# ES_Daisy_Field_Rev4.net
KiCad netlist of a schematic drawn in EAGLE
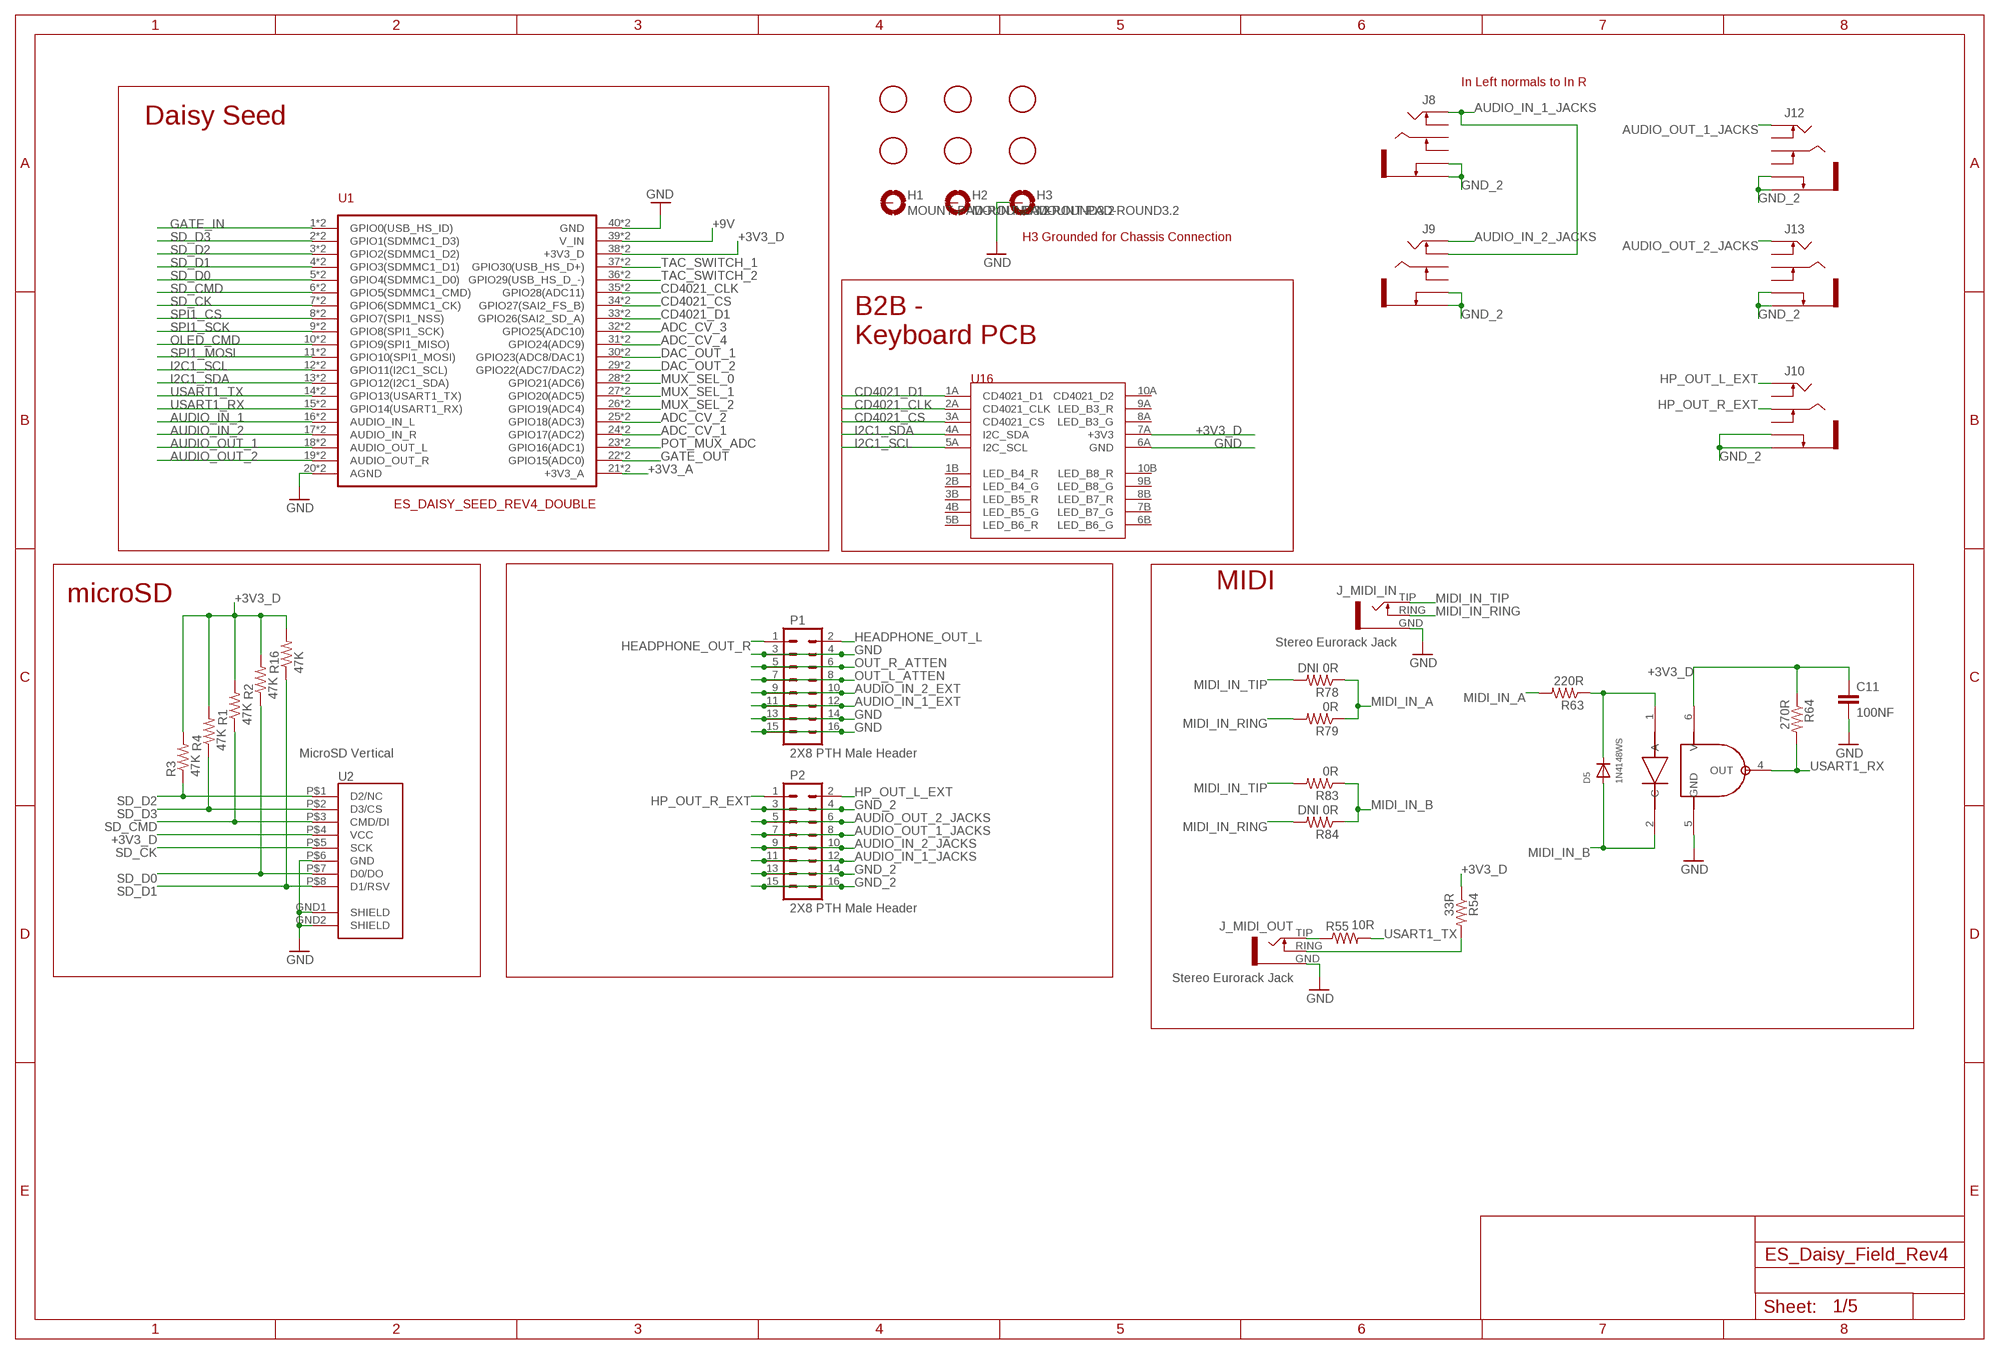
[diagram p0: schematic, sheet 1]
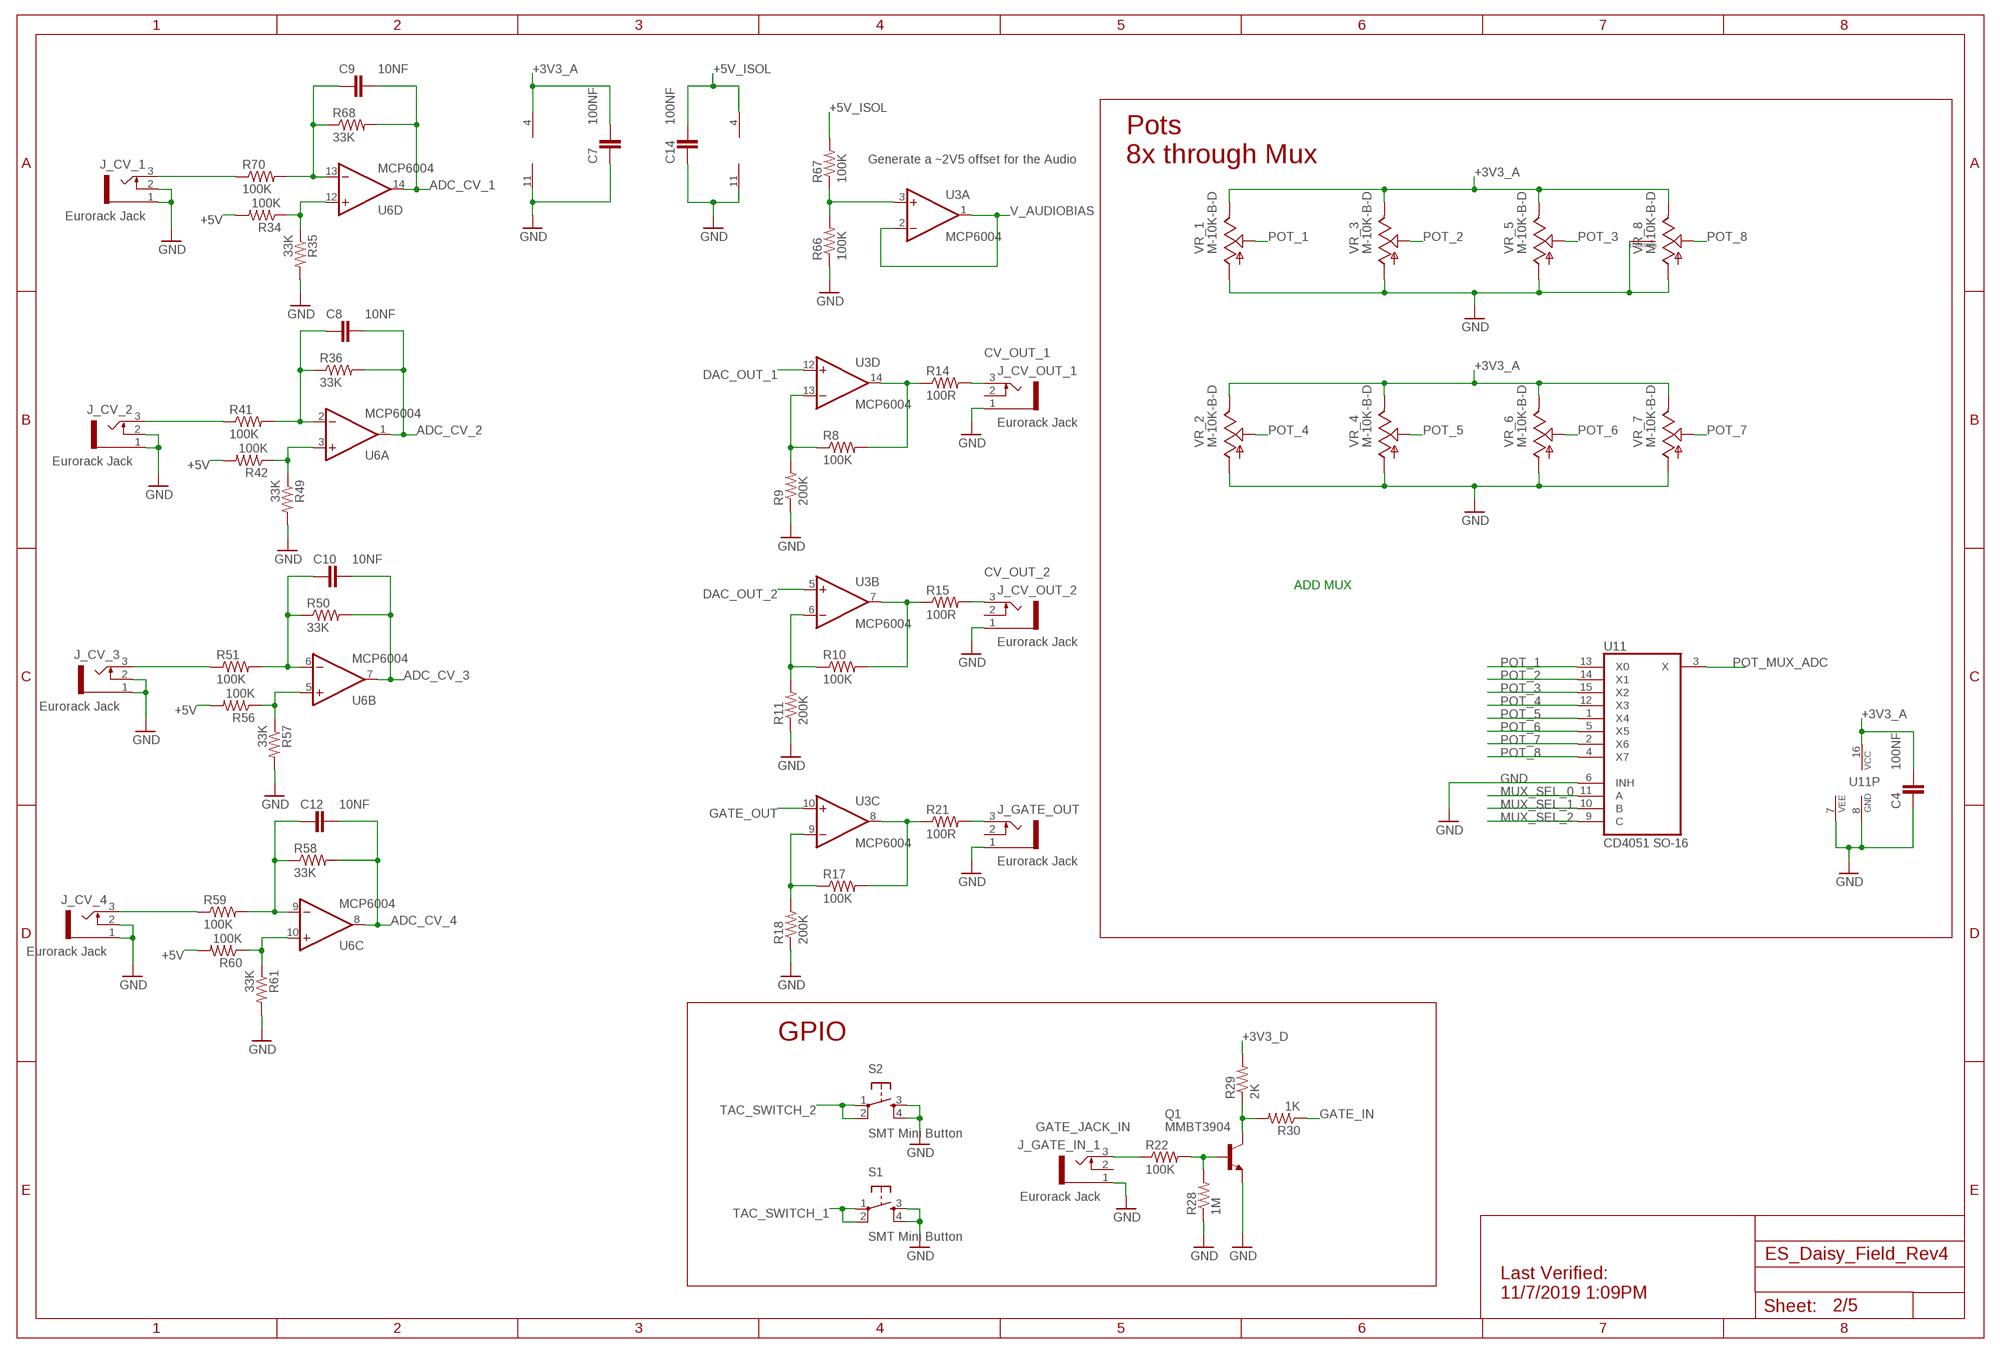
[diagram p1: schematic, sheet 2]
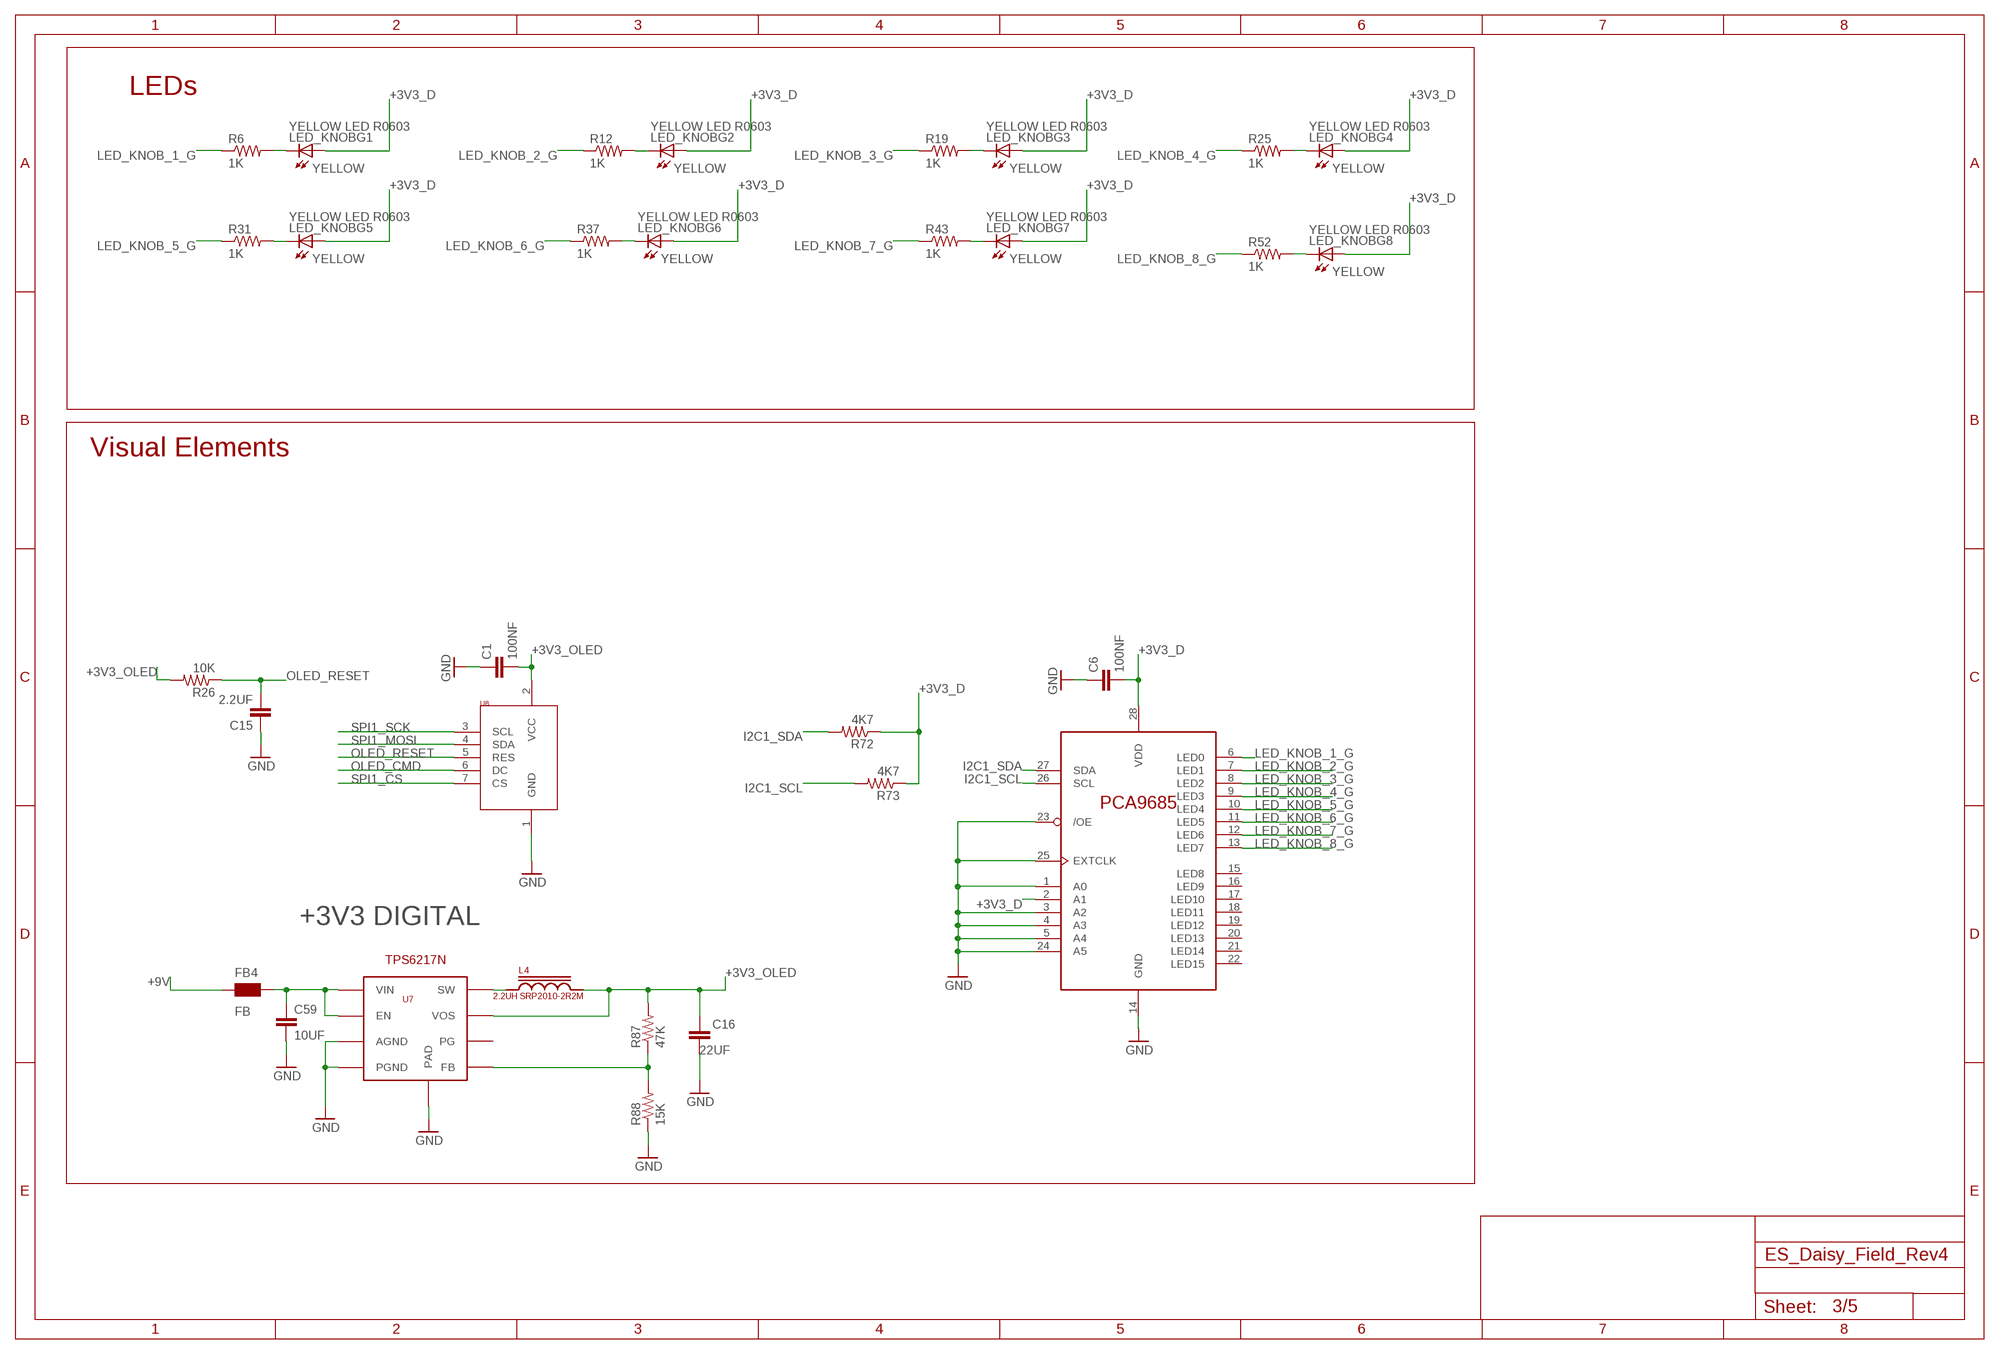
[diagram p2: schematic, sheet 3]
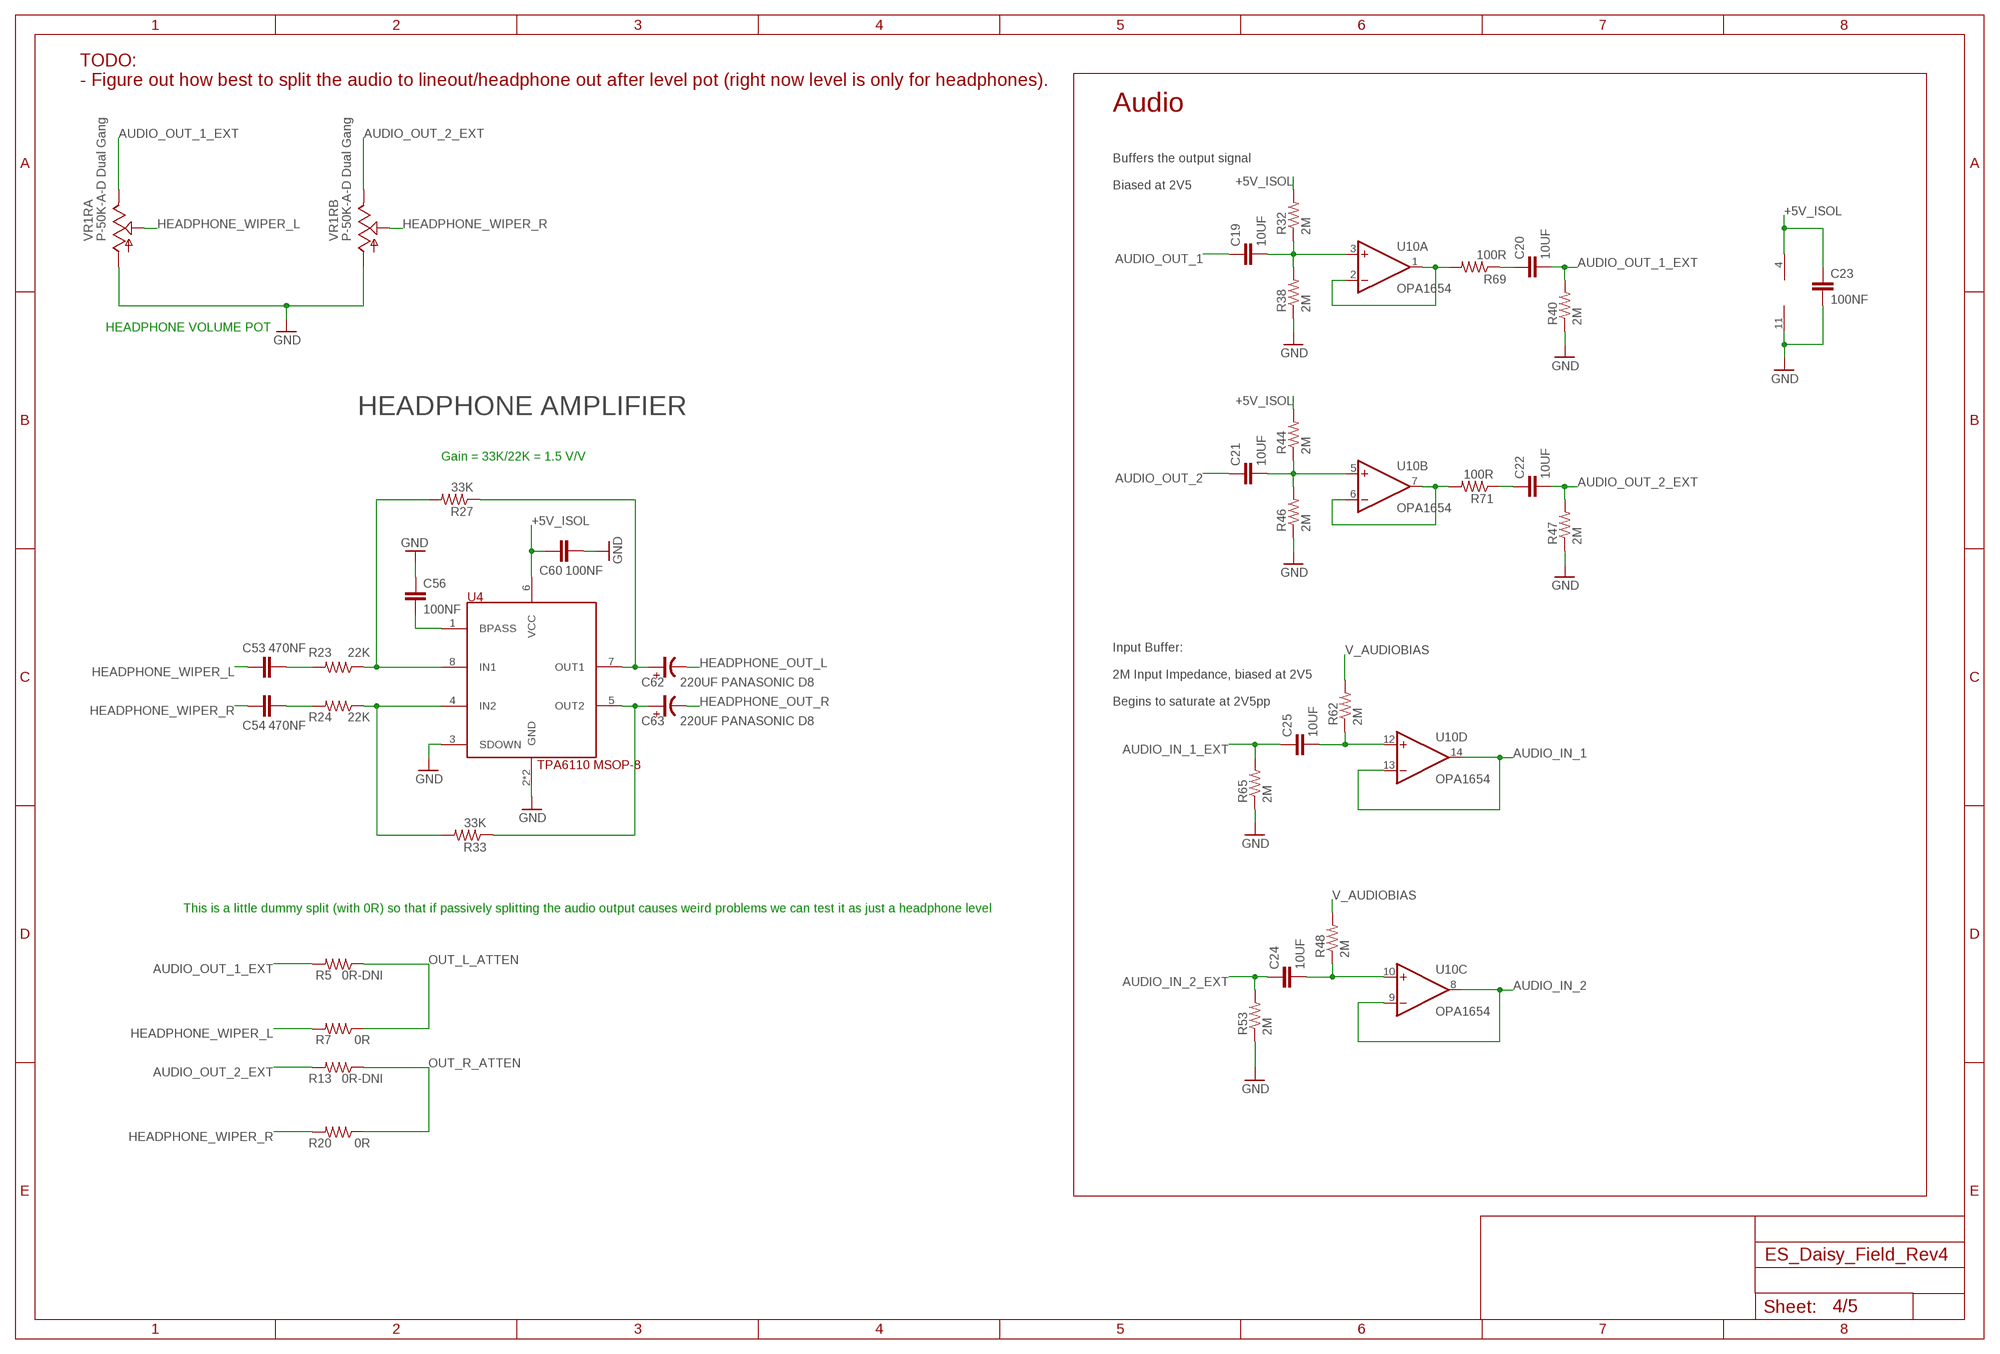
[diagram p3: schematic, sheet 4]
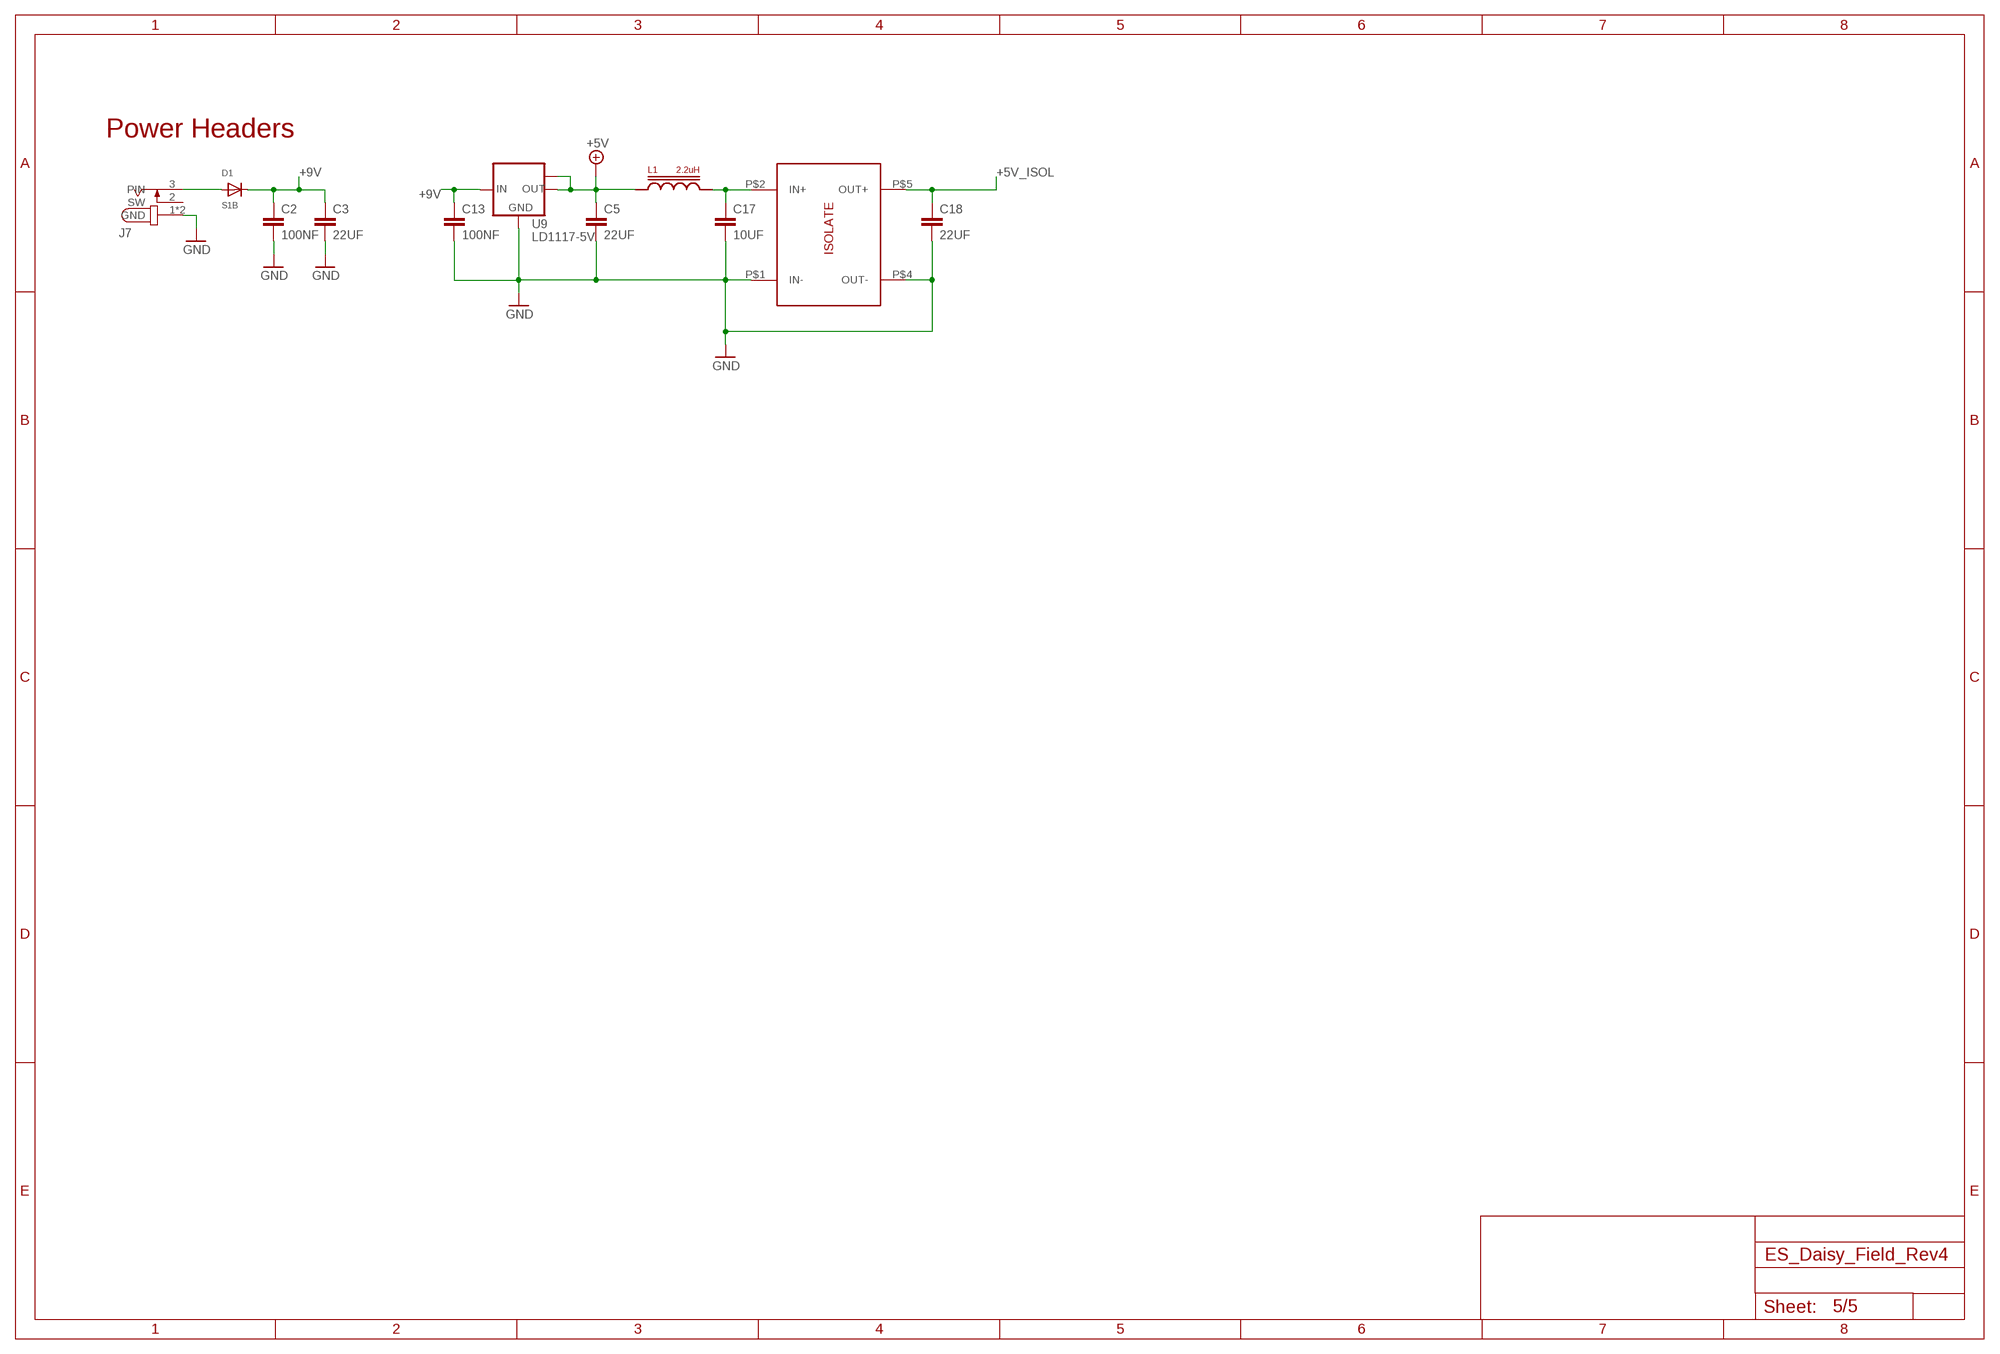
[diagram p4: schematic, sheet 5]

(export (version "E")
  (design (tool "Eeschema 10.0.6"))
  (components
    (comp (ref "C4")
      (value "100NF")
      (footprint "eagle-import:C0603")
      (libsource (lib "eagle-import") (part "C-EUC0603"))
    )
    (comp (ref "C7")
      (value "100NF")
      (footprint "eagle-import:C0603")
      (libsource (lib "eagle-import") (part "C-EUC0603"))
    )
    (comp (ref "C8")
      (value "10NF")
      (footprint "eagle-import:C0603")
      (libsource (lib "eagle-import") (part "C-EUC0603"))
    )
    (comp (ref "C9")
      (value "10NF")
      (footprint "eagle-import:C0603")
      (libsource (lib "eagle-import") (part "C-EUC0603"))
    )
    (comp (ref "C10")
      (value "10NF")
      (footprint "eagle-import:C0603")
      (libsource (lib "eagle-import") (part "C-EUC0603"))
    )
    (comp (ref "C12")
      (value "10NF")
      (footprint "eagle-import:C0603")
      (libsource (lib "eagle-import") (part "C-EUC0603"))
    )
    (comp (ref "C14")
      (value "100NF")
      (footprint "eagle-import:C0603")
      (libsource (lib "eagle-import") (part "C-EUC0603"))
    )
    (comp (ref "J_CV_1")
      (value "Eurorack Jack")
      (footprint "eagle-import:SMT_JACK")
      (libsource (lib "eagle-import") (part "EURO_JACK_SMT"))
    )
    (comp (ref "J_CV_2")
      (value "Eurorack Jack")
      (footprint "eagle-import:SMT_JACK")
      (libsource (lib "eagle-import") (part "EURO_JACK_SMT"))
    )
    (comp (ref "J_CV_3")
      (value "Eurorack Jack")
      (footprint "eagle-import:SMT_JACK")
      (libsource (lib "eagle-import") (part "EURO_JACK_SMT"))
    )
    (comp (ref "J_CV_4")
      (value "Eurorack Jack")
      (footprint "eagle-import:SMT_JACK")
      (libsource (lib "eagle-import") (part "EURO_JACK_SMT"))
    )
    (comp (ref "J_CV_OUT_1")
      (value "Eurorack Jack")
      (footprint "eagle-import:SMT_JACK")
      (libsource (lib "eagle-import") (part "EURO_JACK_SMT"))
    )
    (comp (ref "J_CV_OUT_2")
      (value "Eurorack Jack")
      (footprint "eagle-import:SMT_JACK")
      (libsource (lib "eagle-import") (part "EURO_JACK_SMT"))
    )
    (comp (ref "J_GATE_IN_1")
      (value "Eurorack Jack")
      (footprint "eagle-import:SMT_JACK")
      (libsource (lib "eagle-import") (part "EURO_JACK_SMT"))
    )
    (comp (ref "J_GATE_OUT")
      (value "Eurorack Jack")
      (footprint "eagle-import:SMT_JACK")
      (libsource (lib "eagle-import") (part "EURO_JACK_SMT"))
    )
    (comp (ref "Q1")
      (value "MMBT3904")
      (footprint "eagle-import:SOT23-BEC")
      (libsource (lib "eagle-import") (part "NPNSOT23-BEC"))
    )
    (comp (ref "R8")
      (value "100K")
      (footprint "eagle-import:R0603")
      (libsource (lib "eagle-import") (part "R-US_R0603"))
    )
    (comp (ref "R9")
      (value "200K")
      (footprint "eagle-import:R0603")
      (libsource (lib "eagle-import") (part "R-US_R0603"))
    )
    (comp (ref "R10")
      (value "100K")
      (footprint "eagle-import:R0603")
      (libsource (lib "eagle-import") (part "R-US_R0603"))
    )
    (comp (ref "R11")
      (value "200K")
      (footprint "eagle-import:R0603")
      (libsource (lib "eagle-import") (part "R-US_R0603"))
    )
    (comp (ref "R14")
      (value "100R")
      (footprint "eagle-import:R0603")
      (libsource (lib "eagle-import") (part "R-US_R0603"))
    )
    (comp (ref "R15")
      (value "100R")
      (footprint "eagle-import:R0603")
      (libsource (lib "eagle-import") (part "R-US_R0603"))
    )
    (comp (ref "R17")
      (value "100K")
      (footprint "eagle-import:R0603")
      (libsource (lib "eagle-import") (part "R-US_R0603"))
    )
    (comp (ref "R18")
      (value "200K")
      (footprint "eagle-import:R0603")
      (libsource (lib "eagle-import") (part "R-US_R0603"))
    )
    (comp (ref "R21")
      (value "100R")
      (footprint "eagle-import:R0603")
      (libsource (lib "eagle-import") (part "R-US_R0603"))
    )
    (comp (ref "R22")
      (value "100K")
      (footprint "eagle-import:R0603")
      (libsource (lib "eagle-import") (part "R-US_R0603"))
    )
    (comp (ref "R28")
      (value "1M")
      (footprint "eagle-import:R0603")
      (libsource (lib "eagle-import") (part "R-US_R0603"))
    )
    (comp (ref "R29")
      (value "2K")
      (footprint "eagle-import:R0603")
      (libsource (lib "eagle-import") (part "R-US_R0603"))
    )
    (comp (ref "R30")
      (value "1K")
      (footprint "eagle-import:R0603")
      (libsource (lib "eagle-import") (part "R-US_R0603"))
    )
    (comp (ref "R34")
      (value "100K")
      (footprint "eagle-import:R0603")
      (libsource (lib "eagle-import") (part "R-US_R0603"))
    )
    (comp (ref "R35")
      (value "33K")
      (footprint "eagle-import:R0603")
      (libsource (lib "eagle-import") (part "R-US_R0603"))
    )
    (comp (ref "R36")
      (value "33K")
      (footprint "eagle-import:R0603")
      (libsource (lib "eagle-import") (part "R-US_R0603"))
    )
    (comp (ref "R41")
      (value "100K")
      (footprint "eagle-import:R0603")
      (libsource (lib "eagle-import") (part "R-US_R0603"))
    )
    (comp (ref "R42")
      (value "100K")
      (footprint "eagle-import:R0603")
      (libsource (lib "eagle-import") (part "R-US_R0603"))
    )
    (comp (ref "R49")
      (value "33K")
      (footprint "eagle-import:R0603")
      (libsource (lib "eagle-import") (part "R-US_R0603"))
    )
    (comp (ref "R50")
      (value "33K")
      (footprint "eagle-import:R0603")
      (libsource (lib "eagle-import") (part "R-US_R0603"))
    )
    (comp (ref "R51")
      (value "100K")
      (footprint "eagle-import:R0603")
      (libsource (lib "eagle-import") (part "R-US_R0603"))
    )
    (comp (ref "R56")
      (value "100K")
      (footprint "eagle-import:R0603")
      (libsource (lib "eagle-import") (part "R-US_R0603"))
    )
    (comp (ref "R57")
      (value "33K")
      (footprint "eagle-import:R0603")
      (libsource (lib "eagle-import") (part "R-US_R0603"))
    )
    (comp (ref "R58")
      (value "33K")
      (footprint "eagle-import:R0603")
      (libsource (lib "eagle-import") (part "R-US_R0603"))
    )
    (comp (ref "R59")
      (value "100K")
      (footprint "eagle-import:R0603")
      (libsource (lib "eagle-import") (part "R-US_R0603"))
    )
    (comp (ref "R60")
      (value "100K")
      (footprint "eagle-import:R0603")
      (libsource (lib "eagle-import") (part "R-US_R0603"))
    )
    (comp (ref "R61")
      (value "33K")
      (footprint "eagle-import:R0603")
      (libsource (lib "eagle-import") (part "R-US_R0603"))
    )
    (comp (ref "R66")
      (value "100K")
      (footprint "eagle-import:R0603")
      (libsource (lib "eagle-import") (part "R-US_R0603"))
    )
    (comp (ref "R67")
      (value "100K")
      (footprint "eagle-import:R0603")
      (libsource (lib "eagle-import") (part "R-US_R0603"))
    )
    (comp (ref "R68")
      (value "33K")
      (footprint "eagle-import:R0603")
      (libsource (lib "eagle-import") (part "R-US_R0603"))
    )
    (comp (ref "R70")
      (value "100K")
      (footprint "eagle-import:R0603")
      (libsource (lib "eagle-import") (part "R-US_R0603"))
    )
    (comp (ref "S1")
      (value "SMT Mini Button")
      (footprint "eagle-import:TL3301SPF160QJ")
      (fields (field (name "MPN") "TL3301SPF160QJ"))
      (libsource (lib "eagle-import") (part "TAC_SWITCH_SMT"))
    )
    (comp (ref "S2")
      (value "SMT Mini Button")
      (footprint "eagle-import:TL3301SPF160QJ")
      (fields (field (name "MPN") "TL3301SPF160QJ"))
      (libsource (lib "eagle-import") (part "TAC_SWITCH_SMT"))
    )
    (comp (ref "U3")
      (value "MCP6004")
      (footprint "eagle-import:TSSOP-14")
      (fields (field (name "MPN") "MCP6004T-E/ST"))
      (libsource (lib "eagle-import") (part "MCP6004_TSSOP-14"))
    )
    (comp (ref "U6")
      (value "MCP6004")
      (footprint "eagle-import:TSSOP-14")
      (fields (field (name "MPN") "MCP6004T-E/ST"))
      (libsource (lib "eagle-import") (part "MCP6004_TSSOP-14"))
    )
    (comp (ref "U11")
      (value "CD4051 SO-16")
      (footprint "eagle-import:SO-16")
      (libsource (lib "eagle-import") (part "4051D"))
    )
    (comp (ref "VR_1")
      (value "M-10K-B-D")
      (footprint "eagle-import:9MM_SNAP-IN_POT_SILK")
      (libsource (lib "eagle-import") (part "POT_9MM_SNAP-IN__"))
    )
    (comp (ref "VR_2")
      (value "M-10K-B-D")
      (footprint "eagle-import:9MM_SNAP-IN_POT_SILK")
      (libsource (lib "eagle-import") (part "POT_9MM_SNAP-IN__"))
    )
    (comp (ref "VR_3")
      (value "M-10K-B-D")
      (footprint "eagle-import:9MM_SNAP-IN_POT_SILK")
      (libsource (lib "eagle-import") (part "POT_9MM_SNAP-IN__"))
    )
    (comp (ref "VR_4")
      (value "M-10K-B-D")
      (footprint "eagle-import:9MM_SNAP-IN_POT_SILK")
      (libsource (lib "eagle-import") (part "POT_9MM_SNAP-IN__"))
    )
    (comp (ref "VR_5")
      (value "M-10K-B-D")
      (footprint "eagle-import:9MM_SNAP-IN_POT_SILK")
      (libsource (lib "eagle-import") (part "POT_9MM_SNAP-IN__"))
    )
    (comp (ref "VR_6")
      (value "M-10K-B-D")
      (footprint "eagle-import:9MM_SNAP-IN_POT_SILK")
      (libsource (lib "eagle-import") (part "POT_9MM_SNAP-IN__"))
    )
    (comp (ref "VR_7")
      (value "M-10K-B-D")
      (footprint "eagle-import:9MM_SNAP-IN_POT_SILK")
      (libsource (lib "eagle-import") (part "POT_9MM_SNAP-IN__"))
    )
    (comp (ref "VR_8")
      (value "M-10K-B-D")
      (footprint "eagle-import:9MM_SNAP-IN_POT_SILK")
      (libsource (lib "eagle-import") (part "POT_9MM_CHASSIS_"))
    )
    (comp (ref "C19")
      (value "10UF")
      (footprint "eagle-import:C0805")
      (libsource (lib "eagle-import") (part "C-EUC0805"))
    )
    (comp (ref "C20")
      (value "10UF")
      (footprint "eagle-import:C0805")
      (libsource (lib "eagle-import") (part "C-EUC0805"))
    )
    (comp (ref "C21")
      (value "10UF")
      (footprint "eagle-import:C0805")
      (libsource (lib "eagle-import") (part "C-EUC0805"))
    )
    (comp (ref "C22")
      (value "10UF")
      (footprint "eagle-import:C0805")
      (libsource (lib "eagle-import") (part "C-EUC0805"))
    )
    (comp (ref "C23")
      (value "100NF")
      (footprint "eagle-import:C0603")
      (libsource (lib "eagle-import") (part "C-EUC0603"))
    )
    (comp (ref "C24")
      (value "10UF")
      (footprint "eagle-import:C0805")
      (libsource (lib "eagle-import") (part "C-EUC0805"))
    )
    (comp (ref "C25")
      (value "10UF")
      (footprint "eagle-import:C0805")
      (libsource (lib "eagle-import") (part "C-EUC0805"))
    )
    (comp (ref "C53")
      (value "470NF")
      (footprint "eagle-import:C0603")
      (libsource (lib "eagle-import") (part "C-EUC0603"))
    )
    (comp (ref "C54")
      (value "470NF")
      (footprint "eagle-import:C0603")
      (libsource (lib "eagle-import") (part "C-EUC0603"))
    )
    (comp (ref "C56")
      (value "100NF")
      (footprint "eagle-import:C0603")
      (libsource (lib "eagle-import") (part "C-EUC0603"))
    )
    (comp (ref "C60")
      (value "100NF")
      (footprint "eagle-import:C0603")
      (libsource (lib "eagle-import") (part "C-EUC0603"))
    )
    (comp (ref "C62")
      (value "220UF PANASONIC D8")
      (footprint "eagle-import:PANASONIC_D")
      (libsource (lib "eagle-import") (part "C-EU-POL_D"))
    )
    (comp (ref "C63")
      (value "220UF PANASONIC D8")
      (footprint "eagle-import:PANASONIC_D")
      (libsource (lib "eagle-import") (part "C-EU-POL_D"))
    )
    (comp (ref "R5")
      (value "0R-DNI")
      (footprint "eagle-import:R0603")
      (libsource (lib "eagle-import") (part "R-US_R0603"))
    )
    (comp (ref "R7")
      (value "0R")
      (footprint "eagle-import:R0603")
      (libsource (lib "eagle-import") (part "R-US_R0603"))
    )
    (comp (ref "R13")
      (value "0R-DNI")
      (footprint "eagle-import:R0603")
      (libsource (lib "eagle-import") (part "R-US_R0603"))
    )
    (comp (ref "R20")
      (value "0R")
      (footprint "eagle-import:R0603")
      (libsource (lib "eagle-import") (part "R-US_R0603"))
    )
    (comp (ref "R23")
      (value "22K")
      (footprint "eagle-import:R0603")
      (libsource (lib "eagle-import") (part "R-US_R0603"))
    )
    (comp (ref "R24")
      (value "22K")
      (footprint "eagle-import:R0603")
      (libsource (lib "eagle-import") (part "R-US_R0603"))
    )
    (comp (ref "R27")
      (value "33K")
      (footprint "eagle-import:R0603")
      (libsource (lib "eagle-import") (part "R-US_R0603"))
    )
    (comp (ref "R32")
      (value "2M")
      (footprint "eagle-import:R0603")
      (libsource (lib "eagle-import") (part "R-US_R0603"))
    )
    (comp (ref "R33")
      (value "33K")
      (footprint "eagle-import:R0603")
      (libsource (lib "eagle-import") (part "R-US_R0603"))
    )
    (comp (ref "R38")
      (value "2M")
      (footprint "eagle-import:R0603")
      (libsource (lib "eagle-import") (part "R-US_R0603"))
    )
    (comp (ref "R40")
      (value "2M")
      (footprint "eagle-import:R0603")
      (libsource (lib "eagle-import") (part "R-US_R0603"))
    )
    (comp (ref "R44")
      (value "2M")
      (footprint "eagle-import:R0603")
      (libsource (lib "eagle-import") (part "R-US_R0603"))
    )
    (comp (ref "R46")
      (value "2M")
      (footprint "eagle-import:R0603")
      (libsource (lib "eagle-import") (part "R-US_R0603"))
    )
    (comp (ref "R47")
      (value "2M")
      (footprint "eagle-import:R0603")
      (libsource (lib "eagle-import") (part "R-US_R0603"))
    )
    (comp (ref "R48")
      (value "2M")
      (footprint "eagle-import:R0603")
      (libsource (lib "eagle-import") (part "R-US_R0603"))
    )
    (comp (ref "R53")
      (value "2M")
      (footprint "eagle-import:R0603")
      (libsource (lib "eagle-import") (part "R-US_R0603"))
    )
    (comp (ref "R62")
      (value "2M")
      (footprint "eagle-import:R0603")
      (libsource (lib "eagle-import") (part "R-US_R0603"))
    )
    (comp (ref "R65")
      (value "2M")
      (footprint "eagle-import:R0603")
      (libsource (lib "eagle-import") (part "R-US_R0603"))
    )
    (comp (ref "R69")
      (value "100R")
      (footprint "eagle-import:R0603")
      (libsource (lib "eagle-import") (part "R-US_R0603"))
    )
    (comp (ref "R71")
      (value "100R")
      (footprint "eagle-import:R0603")
      (libsource (lib "eagle-import") (part "R-US_R0603"))
    )
    (comp (ref "U4")
      (value "TPA6110 MSOP-8")
      (footprint "eagle-import:MSOP_8_PWRPAD")
      (libsource (lib "eagle-import") (part "TPA6110MSOP"))
    )
    (comp (ref "U10")
      (value "OPA1654")
      (footprint "eagle-import:TSSOP-14")
      (libsource (lib "eagle-import") (part "OPA1654_TSSOP-14"))
    )
    (comp (ref "VR1")
      (value "P-50K-A-D Dual Gang")
      (footprint "eagle-import:BOURNS_PTV112_SILK")
      (libsource (lib "eagle-import") (part "POT_DUAL_GANG"))
    )
    (comp (ref "C2")
      (value "100NF")
      (footprint "eagle-import:C0603")
      (libsource (lib "eagle-import") (part "C-EUC0603"))
    )
    (comp (ref "C3")
      (value "22UF")
      (footprint "eagle-import:C1206")
      (libsource (lib "eagle-import") (part "C-EUC1206"))
    )
    (comp (ref "C5")
      (value "22UF")
      (footprint "eagle-import:C0805")
      (libsource (lib "eagle-import") (part "C-EUC0805"))
    )
    (comp (ref "C13")
      (value "100NF")
      (footprint "eagle-import:C0603")
      (libsource (lib "eagle-import") (part "C-EUC0603"))
    )
    (comp (ref "C17")
      (value "10UF")
      (footprint "eagle-import:C0805")
      (libsource (lib "eagle-import") (part "C-EUC0805"))
    )
    (comp (ref "C18")
      (value "22UF")
      (footprint "eagle-import:C1206")
      (libsource (lib "eagle-import") (part "C-EUC1206"))
    )
    (comp (ref "D1")
      (value "S1B")
      (footprint "eagle-import:SMADIODE")
      (libsource (lib "eagle-import") (part "S1B"))
    )
    (comp (ref "J7")
      (value "SMT GUITAR DC JACK")
      (footprint "eagle-import:WQP-DC0500")
      (libsource (lib "eagle-import") (part "GUITAR_DC_JACK"))
    )
    (comp (ref "L1")
      (value "2.2uH")
      (footprint "eagle-import:BOURNS_SRP2010")
      (libsource (lib "eagle-import") (part "INDUCTORS"))
    )
    (comp (ref "U$4")
      (value "POWER_ISOLATE")
      (footprint "eagle-import:XP_POWER_ISEXXXXA")
      (fields (field (name "MPN") "ISE2405A"))
      (libsource (lib "eagle-import") (part "POWER_ISOLATE"))
    )
    (comp (ref "U9")
      (value "LD1117-5V")
      (footprint "eagle-import:SOT223")
      (fields (field (name "MPN") "LD1117S50CTR"))
      (libsource (lib "eagle-import") (part "LD1117-5V"))
    )
    (comp (ref "C11")
      (value "100NF")
      (footprint "eagle-import:C0603")
      (libsource (lib "eagle-import") (part "C-EUC0603"))
    )
    (comp (ref "D5")
      (value "1N4148WS")
      (footprint "eagle-import:SOD-323F")
      (libsource (lib "eagle-import") (part "DIODE_SOD-323F"))
    )
    (comp (ref "FD1")
      (value "FIDUCIAL")
      (footprint "eagle-import:FIDUCIAL_1MM")
      (libsource (lib "eagle-import") (part "FIDUCIAL"))
    )
    (comp (ref "FD2")
      (value "FIDUCIAL")
      (footprint "eagle-import:FIDUCIAL_1MM")
      (libsource (lib "eagle-import") (part "FIDUCIAL"))
    )
    (comp (ref "FD3")
      (value "FIDUCIAL")
      (footprint "eagle-import:FIDUCIAL_1MM")
      (libsource (lib "eagle-import") (part "FIDUCIAL"))
    )
    (comp (ref "FD4")
      (value "FIDUCIAL")
      (footprint "eagle-import:FIDUCIAL_1MM")
      (libsource (lib "eagle-import") (part "FIDUCIAL"))
    )
    (comp (ref "FD5")
      (value "FIDUCIAL")
      (footprint "eagle-import:FIDUCIAL_1MM")
      (libsource (lib "eagle-import") (part "FIDUCIAL"))
    )
    (comp (ref "FD6")
      (value "FIDUCIAL")
      (footprint "eagle-import:FIDUCIAL_1MM")
      (libsource (lib "eagle-import") (part "FIDUCIAL"))
    )
    (comp (ref "H1")
      (value "MOUNT-PAD-ROUND3.2")
      (footprint "eagle-import:32-PAD")
      (libsource (lib "eagle-import") (part "MOUNT-PAD-ROUND3.2"))
    )
    (comp (ref "H2")
      (value "MOUNT-PAD-ROUND3.2")
      (footprint "eagle-import:32-PAD")
      (libsource (lib "eagle-import") (part "MOUNT-PAD-ROUND3.2"))
    )
    (comp (ref "H3")
      (value "MOUNT-PAD-ROUND3.2")
      (footprint "eagle-import:32-PAD")
      (libsource (lib "eagle-import") (part "MOUNT-PAD-ROUND3.2"))
    )
    (comp (ref "J8")
      (value "PTH Switching Stereo Guitar Jack")
      (footprint "eagle-import:WQP-PJ6110")
      (libsource (lib "eagle-import") (part "JACK_TRS_SWITCHING_WQP-PJ6110"))
    )
    (comp (ref "J9")
      (value "PTH Switching Stereo Guitar Jack")
      (footprint "eagle-import:WQP-PJ6110")
      (libsource (lib "eagle-import") (part "JACK_TRS_SWITCHING_WQP-PJ6110"))
    )
    (comp (ref "J10")
      (value "PTH Switching Stereo Guitar Jack")
      (footprint "eagle-import:WQP-PJ6110")
      (libsource (lib "eagle-import") (part "JACK_TRS_SWITCHING_WQP-PJ6110"))
    )
    (comp (ref "J12")
      (value "PTH Switching Stereo Guitar Jack")
      (footprint "eagle-import:WQP-PJ6110")
      (libsource (lib "eagle-import") (part "JACK_TRS_SWITCHING_WQP-PJ6110"))
    )
    (comp (ref "J13")
      (value "PTH Switching Stereo Guitar Jack")
      (footprint "eagle-import:WQP-PJ6110")
      (libsource (lib "eagle-import") (part "JACK_TRS_SWITCHING_WQP-PJ6110"))
    )
    (comp (ref "J_MIDI_IN")
      (value "Stereo Eurorack Jack")
      (footprint "eagle-import:STEREO_JACK_3.5MM")
      (libsource (lib "eagle-import") (part "STEREO_JACK"))
    )
    (comp (ref "J_MIDI_OUT")
      (value "Stereo Eurorack Jack")
      (footprint "eagle-import:STEREO_JACK_3.5MM")
      (libsource (lib "eagle-import") (part "STEREO_JACK"))
    )
    (comp (ref "P1")
      (value "2X8 PTH Male Header")
      (footprint "eagle-import:2X8_LOCK")
      (libsource (lib "eagle-import") (part "M08X2?_LOCK_SILK"))
    )
    (comp (ref "P2")
      (value "2X8 PTH Male Header")
      (footprint "eagle-import:2X8_LOCK")
      (libsource (lib "eagle-import") (part "M08X2?_LOCK_SILK"))
    )
    (comp (ref "R1")
      (value "47K")
      (footprint "eagle-import:R0603")
      (libsource (lib "eagle-import") (part "R-US_R0603"))
    )
    (comp (ref "R2")
      (value "47K")
      (footprint "eagle-import:R0603")
      (libsource (lib "eagle-import") (part "R-US_R0603"))
    )
    (comp (ref "R3")
      (value "47K")
      (footprint "eagle-import:R0603")
      (libsource (lib "eagle-import") (part "R-US_R0603"))
    )
    (comp (ref "R4")
      (value "47K")
      (footprint "eagle-import:R0603")
      (libsource (lib "eagle-import") (part "R-US_R0603"))
    )
    (comp (ref "R16")
      (value "47K")
      (footprint "eagle-import:R0603")
      (libsource (lib "eagle-import") (part "R-US_R0603"))
    )
    (comp (ref "R54")
      (value "33R")
      (footprint "eagle-import:R0603")
      (libsource (lib "eagle-import") (part "R-US_R0603"))
    )
    (comp (ref "R55")
      (value "10R")
      (footprint "eagle-import:R0603")
      (libsource (lib "eagle-import") (part "R-US_R0603"))
    )
    (comp (ref "R63")
      (value "220R")
      (footprint "eagle-import:R0603")
      (libsource (lib "eagle-import") (part "R-US_R0603"))
    )
    (comp (ref "R64")
      (value "270R")
      (footprint "eagle-import:R0603")
      (libsource (lib "eagle-import") (part "R-US_R0603"))
    )
    (comp (ref "R78")
      (value "DNI 0R")
      (footprint "eagle-import:R0603")
      (libsource (lib "eagle-import") (part "R-US_R0603"))
    )
    (comp (ref "R79")
      (value "0R")
      (footprint "eagle-import:R0603")
      (libsource (lib "eagle-import") (part "R-US_R0603"))
    )
    (comp (ref "R83")
      (value "0R")
      (footprint "eagle-import:R0603")
      (libsource (lib "eagle-import") (part "R-US_R0603"))
    )
    (comp (ref "R84")
      (value "DNI 0R")
      (footprint "eagle-import:R0603")
      (libsource (lib "eagle-import") (part "R-US_R0603"))
    )
    (comp (ref "U1")
      (value "ES_DAISY_SEED_REV4_DOUBLE")
      (footprint "eagle-import:ES_DAISY_SEED_DOUBLE")
      (libsource (lib "eagle-import") (part "ES_DAISY_SEED_REV4_DOUBLE"))
    )
    (comp (ref "U2")
      (value "MicroSD Vertical")
      (footprint "eagle-import:VERT_MICROSD_CENTERED")
      (libsource (lib "eagle-import") (part "MICRO_SD_CARDCENTERED"))
    )
    (comp (ref "U15")
      (value "OPTO ISOLATOR")
      (footprint "eagle-import:DIL06_GULLWING")
      (fields (field (name "MPN") "H11L1SR2M"))
      (libsource (lib "eagle-import") (part "OPTOISOLATOR_H11L1M"))
    )
    (comp (ref "U16")
      (value "ES_KEYBOARD_SM_REV2_ALIGNED")
      (footprint "eagle-import:ES_KEYBOARD_SM_REV2_ALIGNED")
      (libsource (lib "eagle-import") (part "ES_KEYBOARD_SM_REV2_ALIGNED"))
    )
    (comp (ref "C1")
      (value "100NF")
      (footprint "eagle-import:C0603")
      (libsource (lib "eagle-import") (part "C-EUC0603"))
    )
    (comp (ref "C6")
      (value "100NF")
      (footprint "eagle-import:C0603")
      (libsource (lib "eagle-import") (part "C-EUC0603"))
    )
    (comp (ref "C15")
      (value "2.2UF")
      (footprint "eagle-import:C0603")
      (libsource (lib "eagle-import") (part "C-EUC0603"))
    )
    (comp (ref "C16")
      (value "22UF")
      (footprint "eagle-import:C1206")
      (libsource (lib "eagle-import") (part "C-EUC1206"))
    )
    (comp (ref "C59")
      (value "10UF")
      (footprint "eagle-import:C0805")
      (libsource (lib "eagle-import") (part "C-EUC0805"))
    )
    (comp (ref "FB4")
      (value "FB")
      (footprint "eagle-import:WUERTH-ELEKTRONIK_0603")
      (fields (field (name "MPN") "MI0603J601R-10"))
      (libsource (lib "eagle-import") (part "FERRITE_BEAD_0603"))
    )
    (comp (ref "L4")
      (value "2.2UH SRP2010-2R2M")
      (footprint "eagle-import:BOURNS_SRP2010")
      (libsource (lib "eagle-import") (part "INDUCTORS"))
    )
    (comp (ref "LED_KNOBG1")
      (value "YELLOW LED R0603")
      (footprint "eagle-import:DIODE_0603")
      (fields (field (name "COLOR") "YELLOW") (field (name "MPN") "APT1608LSYCK/J3-PRV"))
      (libsource (lib "eagle-import") (part "LED_0603_YELLOW"))
    )
    (comp (ref "LED_KNOBG2")
      (value "YELLOW LED R0603")
      (footprint "eagle-import:DIODE_0603")
      (fields (field (name "COLOR") "YELLOW") (field (name "MPN") "APT1608LSYCK/J3-PRV"))
      (libsource (lib "eagle-import") (part "LED_0603_YELLOW"))
    )
    (comp (ref "LED_KNOBG3")
      (value "YELLOW LED R0603")
      (footprint "eagle-import:DIODE_0603")
      (fields (field (name "COLOR") "YELLOW") (field (name "MPN") "APT1608LSYCK/J3-PRV"))
      (libsource (lib "eagle-import") (part "LED_0603_YELLOW"))
    )
    (comp (ref "LED_KNOBG4")
      (value "YELLOW LED R0603")
      (footprint "eagle-import:DIODE_0603")
      (fields (field (name "COLOR") "YELLOW") (field (name "MPN") "APT1608LSYCK/J3-PRV"))
      (libsource (lib "eagle-import") (part "LED_0603_YELLOW"))
    )
    (comp (ref "LED_KNOBG5")
      (value "YELLOW LED R0603")
      (footprint "eagle-import:DIODE_0603")
      (fields (field (name "COLOR") "YELLOW") (field (name "MPN") "APT1608LSYCK/J3-PRV"))
      (libsource (lib "eagle-import") (part "LED_0603_YELLOW"))
    )
    (comp (ref "LED_KNOBG6")
      (value "YELLOW LED R0603")
      (footprint "eagle-import:DIODE_0603")
      (fields (field (name "COLOR") "YELLOW") (field (name "MPN") "APT1608LSYCK/J3-PRV"))
      (libsource (lib "eagle-import") (part "LED_0603_YELLOW"))
    )
    (comp (ref "LED_KNOBG7")
      (value "YELLOW LED R0603")
      (footprint "eagle-import:DIODE_0603")
      (fields (field (name "COLOR") "YELLOW") (field (name "MPN") "APT1608LSYCK/J3-PRV"))
      (libsource (lib "eagle-import") (part "LED_0603_YELLOW"))
    )
    (comp (ref "LED_KNOBG8")
      (value "YELLOW LED R0603")
      (footprint "eagle-import:DIODE_0603")
      (fields (field (name "COLOR") "YELLOW") (field (name "MPN") "APT1608LSYCK/J3-PRV"))
      (libsource (lib "eagle-import") (part "LED_0603_YELLOW"))
    )
    (comp (ref "R6")
      (value "1K")
      (footprint "eagle-import:R0603")
      (libsource (lib "eagle-import") (part "R-US_R0603"))
    )
    (comp (ref "R12")
      (value "1K")
      (footprint "eagle-import:R0603")
      (libsource (lib "eagle-import") (part "R-US_R0603"))
    )
    (comp (ref "R19")
      (value "1K")
      (footprint "eagle-import:R0603")
      (libsource (lib "eagle-import") (part "R-US_R0603"))
    )
    (comp (ref "R25")
      (value "1K")
      (footprint "eagle-import:R0603")
      (libsource (lib "eagle-import") (part "R-US_R0603"))
    )
    (comp (ref "R26")
      (value "10K")
      (footprint "eagle-import:R0603")
      (libsource (lib "eagle-import") (part "R-US_R0603"))
    )
    (comp (ref "R31")
      (value "1K")
      (footprint "eagle-import:R0603")
      (libsource (lib "eagle-import") (part "R-US_R0603"))
    )
    (comp (ref "R37")
      (value "1K")
      (footprint "eagle-import:R0603")
      (libsource (lib "eagle-import") (part "R-US_R0603"))
    )
    (comp (ref "R43")
      (value "1K")
      (footprint "eagle-import:R0603")
      (libsource (lib "eagle-import") (part "R-US_R0603"))
    )
    (comp (ref "R52")
      (value "1K")
      (footprint "eagle-import:R0603")
      (libsource (lib "eagle-import") (part "R-US_R0603"))
    )
    (comp (ref "R72")
      (value "4K7")
      (footprint "eagle-import:R0603")
      (libsource (lib "eagle-import") (part "R-US_R0603"))
    )
    (comp (ref "R73")
      (value "4K7")
      (footprint "eagle-import:R0603")
      (libsource (lib "eagle-import") (part "R-US_R0603"))
    )
    (comp (ref "R87")
      (value "47K")
      (footprint "eagle-import:R0603")
      (libsource (lib "eagle-import") (part "R-US_R0603"))
    )
    (comp (ref "R88")
      (value "15K")
      (footprint "eagle-import:R0603")
      (libsource (lib "eagle-import") (part "R-US_R0603"))
    )
    (comp (ref "U5")
      (value "PCA9685 TSSOP-28")
      (footprint "eagle-import:TSSOP-28")
      (fields (field (name "MPN") "PCA9685PW,118"))
      (libsource (lib "eagle-import") (part "PCA9685PW"))
    )
    (comp (ref "U7")
      (value "TPS62170 WSON-8")
      (footprint "eagle-import:WSON-8")
      (fields (field (name "MPN") "TPS62170"))
      (libsource (lib "eagle-import") (part "TPS6217N"))
    )
    (comp (ref "U8")
      (value "OLED_DISPLAY")
      (footprint "eagle-import:ER-OLEDM015-2")
      (fields (field (name "MPN") "ER-OLEDM015-2W-SPI-I2C"))
      (libsource (lib "eagle-import") (part "OLED_DISPLAY"))
    )
  )
  (nets
    (net (code "1") (name "+3V3_A") (class "Default")
      (node (ref "C4") (pin "2") (pinfunction "2_2") (pintype "passive"))
      (node (ref "C7") (pin "2") (pinfunction "2_2") (pintype "passive"))
      (node (ref "U1") (pin "21") (pinfunction "+3V3_A_21") (pintype "bidirectional"))
      (node (ref "U1") (pin "B21") (pinfunction "+3V3_A_B21") (pintype "bidirectional"))
      (node (ref "U11") (pin "16") (pinfunction "VCC_16") (pintype "power_in"))
      (node (ref "U6") (pin "4") (pinfunction "V+_4") (pintype "power_in"))
      (node (ref "VR_1") (pin "3") (pinfunction "3_3") (pintype "passive"))
      (node (ref "VR_2") (pin "3") (pinfunction "3_3") (pintype "passive"))
      (node (ref "VR_3") (pin "3") (pinfunction "3_3") (pintype "passive"))
      (node (ref "VR_4") (pin "3") (pinfunction "3_3") (pintype "passive"))
      (node (ref "VR_5") (pin "3") (pinfunction "3_3") (pintype "passive"))
      (node (ref "VR_6") (pin "3") (pinfunction "3_3") (pintype "passive"))
      (node (ref "VR_7") (pin "3") (pinfunction "3_3") (pintype "passive"))
      (node (ref "VR_8") (pin "3") (pinfunction "E_3") (pintype "passive"))
    )
    (net (code "2") (name "+3V3_D") (class "Default")
      (node (ref "C11") (pin "1") (pinfunction "1_1") (pintype "passive"))
      (node (ref "C6") (pin "2") (pinfunction "2_2") (pintype "passive"))
      (node (ref "LED_KNOBG1") (pin "ANODE") (pinfunction "A_ANODE") (pintype "passive"))
      (node (ref "LED_KNOBG2") (pin "ANODE") (pinfunction "A_ANODE") (pintype "passive"))
      (node (ref "LED_KNOBG3") (pin "ANODE") (pinfunction "A_ANODE") (pintype "passive"))
      (node (ref "LED_KNOBG4") (pin "ANODE") (pinfunction "A_ANODE") (pintype "passive"))
      (node (ref "LED_KNOBG5") (pin "ANODE") (pinfunction "A_ANODE") (pintype "passive"))
      (node (ref "LED_KNOBG6") (pin "ANODE") (pinfunction "A_ANODE") (pintype "passive"))
      (node (ref "LED_KNOBG7") (pin "ANODE") (pinfunction "A_ANODE") (pintype "passive"))
      (node (ref "LED_KNOBG8") (pin "ANODE") (pinfunction "A_ANODE") (pintype "passive"))
      (node (ref "R1") (pin "2") (pinfunction "2_2") (pintype "passive"))
      (node (ref "R16") (pin "2") (pinfunction "2_2") (pintype "passive"))
      (node (ref "R2") (pin "2") (pinfunction "2_2") (pintype "passive"))
      (node (ref "R29") (pin "2") (pinfunction "2_2") (pintype "passive"))
      (node (ref "R3") (pin "2") (pinfunction "2_2") (pintype "passive"))
      (node (ref "R4") (pin "2") (pinfunction "2_2") (pintype "passive"))
      (node (ref "R54") (pin "1") (pinfunction "1_1") (pintype "passive"))
      (node (ref "R64") (pin "1") (pinfunction "1_1") (pintype "passive"))
      (node (ref "R72") (pin "1") (pinfunction "1_1") (pintype "passive"))
      (node (ref "R73") (pin "1") (pinfunction "1_1") (pintype "passive"))
      (node (ref "U1") (pin "38") (pinfunction "+3V3_D_38") (pintype "bidirectional"))
      (node (ref "U1") (pin "B38") (pinfunction "+3V3_D_B38") (pintype "bidirectional"))
      (node (ref "U15") (pin "6") (pinfunction "V_6") (pintype "bidirectional"))
      (node (ref "U16") (pin "7A") (pinfunction "+3V3_7A") (pintype "bidirectional"))
      (node (ref "U2") (pin "P$4") (pinfunction "VCC_P$4") (pintype "bidirectional"))
      (node (ref "U5") (pin "2") (pinfunction "A1_2") (pintype "bidirectional"))
      (node (ref "U5") (pin "28") (pinfunction "VDD_28") (pintype "power_in"))
    )
    (net (code "3") (name "+3V3_OLED") (class "Default")
      (node (ref "C1") (pin "2") (pinfunction "2_2") (pintype "passive"))
      (node (ref "C16") (pin "1") (pinfunction "1_1") (pintype "passive"))
      (node (ref "L4") (pin "P$2") (pinfunction "P$2_P$2") (pintype "bidirectional"))
      (node (ref "R26") (pin "2") (pinfunction "2_2") (pintype "passive"))
      (node (ref "R87") (pin "2") (pinfunction "2_2") (pintype "passive"))
      (node (ref "U7") (pin "6") (pinfunction "VOS_6") (pintype "bidirectional"))
      (node (ref "U8") (pin "2") (pinfunction "VCC_2") (pintype "bidirectional"))
    )
    (net (code "4") (name "+5V") (class "Default")
      (node (ref "C5") (pin "1") (pinfunction "1_1") (pintype "passive"))
      (node (ref "L1") (pin "P$1") (pinfunction "P$1_P$1") (pintype "bidirectional"))
      (node (ref "R34") (pin "2") (pinfunction "2_2") (pintype "passive"))
      (node (ref "R42") (pin "2") (pinfunction "2_2") (pintype "passive"))
      (node (ref "R56") (pin "2") (pinfunction "2_2") (pintype "passive"))
      (node (ref "R60") (pin "2") (pinfunction "2_2") (pintype "passive"))
      (node (ref "U9") (pin "2") (pinfunction "OUT_2") (pintype "passive"))
      (node (ref "U9") (pin "TAB") (pinfunction "OUT1_TAB") (pintype "passive"))
    )
    (net (code "5") (name "+5V_ISOL") (class "Default")
      (node (ref "C14") (pin "2") (pinfunction "2_2") (pintype "passive"))
      (node (ref "C18") (pin "1") (pinfunction "1_1") (pintype "passive"))
      (node (ref "C23") (pin "1") (pinfunction "1_1") (pintype "passive"))
      (node (ref "C60") (pin "2") (pinfunction "2_2") (pintype "passive"))
      (node (ref "R32") (pin "2") (pinfunction "2_2") (pintype "passive"))
      (node (ref "R44") (pin "2") (pinfunction "2_2") (pintype "passive"))
      (node (ref "R67") (pin "2") (pinfunction "2_2") (pintype "passive"))
      (node (ref "U$4") (pin "P$5") (pinfunction "OUT+_P$5") (pintype "bidirectional"))
      (node (ref "U10") (pin "4") (pinfunction "V+_4") (pintype "power_in"))
      (node (ref "U3") (pin "4") (pinfunction "V+_4") (pintype "power_in"))
      (node (ref "U4") (pin "6") (pinfunction "VCC_6") (pintype "bidirectional"))
    )
    (net (code "6") (name "+9V") (class "Default")
      (node (ref "C13") (pin "1") (pinfunction "1_1") (pintype "passive"))
      (node (ref "C2") (pin "1") (pinfunction "1_1") (pintype "passive"))
      (node (ref "C3") (pin "1") (pinfunction "1_1") (pintype "passive"))
      (node (ref "D1") (pin "C") (pinfunction "C_C") (pintype "passive"))
      (node (ref "FB4") (pin "1") (pinfunction "1_1") (pintype "passive"))
      (node (ref "U1") (pin "39") (pinfunction "V_IN_39") (pintype "bidirectional"))
      (node (ref "U1") (pin "B39") (pinfunction "V_IN_B39") (pintype "bidirectional"))
      (node (ref "U9") (pin "3") (pinfunction "IN_3") (pintype "input"))
    )
    (net (code "7") (name "ADC_CV_1") (class "Default")
      (node (ref "C9") (pin "2") (pinfunction "2_2") (pintype "passive"))
      (node (ref "R68") (pin "2") (pinfunction "2_2") (pintype "passive"))
      (node (ref "U1") (pin "24") (pinfunction "GPIO17(ADC2)_24") (pintype "bidirectional"))
      (node (ref "U1") (pin "B24") (pinfunction "GPIO17(ADC2)_B24") (pintype "bidirectional"))
      (node (ref "U6") (pin "14") (pinfunction "OUT_14") (pintype "output"))
    )
    (net (code "8") (name "ADC_CV_2") (class "Default")
      (node (ref "C8") (pin "2") (pinfunction "2_2") (pintype "passive"))
      (node (ref "R36") (pin "2") (pinfunction "2_2") (pintype "passive"))
      (node (ref "U1") (pin "25") (pinfunction "GPIO18(ADC3)_25") (pintype "bidirectional"))
      (node (ref "U1") (pin "B25") (pinfunction "GPIO18(ADC3)_B25") (pintype "bidirectional"))
      (node (ref "U6") (pin "1") (pinfunction "OUT_1") (pintype "output"))
    )
    (net (code "9") (name "ADC_CV_3") (class "Default")
      (node (ref "C10") (pin "2") (pinfunction "2_2") (pintype "passive"))
      (node (ref "R50") (pin "2") (pinfunction "2_2") (pintype "passive"))
      (node (ref "U1") (pin "32") (pinfunction "GPIO25(ADC10)_32") (pintype "bidirectional"))
      (node (ref "U1") (pin "B32") (pinfunction "GPIO25(ADC10)_B32") (pintype "bidirectional"))
      (node (ref "U6") (pin "7") (pinfunction "OUT_7") (pintype "output"))
    )
    (net (code "10") (name "ADC_CV_4") (class "Default")
      (node (ref "C12") (pin "2") (pinfunction "2_2") (pintype "passive"))
      (node (ref "R58") (pin "2") (pinfunction "2_2") (pintype "passive"))
      (node (ref "U1") (pin "31") (pinfunction "GPIO24(ADC9)_31") (pintype "bidirectional"))
      (node (ref "U1") (pin "B31") (pinfunction "GPIO24(ADC9)_B31") (pintype "bidirectional"))
      (node (ref "U6") (pin "8") (pinfunction "OUT_8") (pintype "output"))
    )
    (net (code "11") (name "AUDIO_IN_1") (class "Default")
      (node (ref "U1") (pin "16") (pinfunction "AUDIO_IN_L_16") (pintype "bidirectional"))
      (node (ref "U1") (pin "B16") (pinfunction "AUDIO_IN_L_B16") (pintype "bidirectional"))
      (node (ref "U10") (pin "13") (pinfunction "-IN_13") (pintype "input"))
      (node (ref "U10") (pin "14") (pinfunction "OUT_14") (pintype "output"))
    )
    (net (code "12") (name "AUDIO_IN_1_EXT") (class "Default")
      (node (ref "C25") (pin "1") (pinfunction "1_1") (pintype "passive"))
      (node (ref "P1") (pin "11") (pinfunction "11_11") (pintype "passive"))
      (node (ref "P1") (pin "12") (pinfunction "12_12") (pintype "passive"))
      (node (ref "R65") (pin "2") (pinfunction "2_2") (pintype "passive"))
    )
    (net (code "13") (name "AUDIO_IN_1_JACKS") (class "Default")
      (node (ref "J8") (pin "2") (pinfunction "TIP_2") (pintype "passive"))
      (node (ref "J9") (pin "5") (pinfunction "TIP_SW_5") (pintype "passive"))
      (node (ref "P2") (pin "11") (pinfunction "11_11") (pintype "passive"))
      (node (ref "P2") (pin "12") (pinfunction "12_12") (pintype "passive"))
    )
    (net (code "14") (name "AUDIO_IN_2") (class "Default")
      (node (ref "U1") (pin "17") (pinfunction "AUDIO_IN_R_17") (pintype "bidirectional"))
      (node (ref "U1") (pin "B17") (pinfunction "AUDIO_IN_R_B17") (pintype "bidirectional"))
      (node (ref "U10") (pin "8") (pinfunction "OUT_8") (pintype "output"))
      (node (ref "U10") (pin "9") (pinfunction "-IN_9") (pintype "input"))
    )
    (net (code "15") (name "AUDIO_IN_2_EXT") (class "Default")
      (node (ref "C24") (pin "1") (pinfunction "1_1") (pintype "passive"))
      (node (ref "P1") (pin "10") (pinfunction "10_10") (pintype "passive"))
      (node (ref "P1") (pin "9") (pinfunction "9_9") (pintype "passive"))
      (node (ref "R53") (pin "2") (pinfunction "2_2") (pintype "passive"))
    )
    (net (code "16") (name "AUDIO_IN_2_JACKS") (class "Default")
      (node (ref "J9") (pin "2") (pinfunction "TIP_2") (pintype "passive"))
      (node (ref "P2") (pin "10") (pinfunction "10_10") (pintype "passive"))
      (node (ref "P2") (pin "9") (pinfunction "9_9") (pintype "passive"))
    )
    (net (code "17") (name "AUDIO_OUT_1") (class "Default")
      (node (ref "C19") (pin "1") (pinfunction "1_1") (pintype "passive"))
      (node (ref "U1") (pin "18") (pinfunction "AUDIO_OUT_L_18") (pintype "bidirectional"))
      (node (ref "U1") (pin "B18") (pinfunction "AUDIO_OUT_L_B18") (pintype "bidirectional"))
    )
    (net (code "18") (name "AUDIO_OUT_1_EXT") (class "Default")
      (node (ref "C20") (pin "2") (pinfunction "2_2") (pintype "passive"))
      (node (ref "R40") (pin "2") (pinfunction "2_2") (pintype "passive"))
      (node (ref "R5") (pin "2") (pinfunction "2_2") (pintype "passive"))
      (node (ref "VR1") (pin "3P") (pinfunction "3_3P") (pintype "passive"))
    )
    (net (code "19") (name "AUDIO_OUT_1_JACKS") (class "Default")
      (node (ref "J12") (pin "2") (pinfunction "TIP_2") (pintype "passive"))
      (node (ref "P2") (pin "7") (pinfunction "7_7") (pintype "passive"))
      (node (ref "P2") (pin "8") (pinfunction "8_8") (pintype "passive"))
    )
    (net (code "20") (name "AUDIO_OUT_2") (class "Default")
      (node (ref "C21") (pin "1") (pinfunction "1_1") (pintype "passive"))
      (node (ref "U1") (pin "19") (pinfunction "AUDIO_OUT_R_19") (pintype "bidirectional"))
      (node (ref "U1") (pin "B19") (pinfunction "AUDIO_OUT_R_B19") (pintype "bidirectional"))
    )
    (net (code "21") (name "AUDIO_OUT_2_EXT") (class "Default")
      (node (ref "C22") (pin "2") (pinfunction "2_2") (pintype "passive"))
      (node (ref "R13") (pin "2") (pinfunction "2_2") (pintype "passive"))
      (node (ref "R47") (pin "2") (pinfunction "2_2") (pintype "passive"))
      (node (ref "VR1") (pin "3") (pinfunction "3_3") (pintype "passive"))
    )
    (net (code "22") (name "AUDIO_OUT_2_JACKS") (class "Default")
      (node (ref "J13") (pin "2") (pinfunction "TIP_2") (pintype "passive"))
      (node (ref "P2") (pin "5") (pinfunction "5_5") (pintype "passive"))
      (node (ref "P2") (pin "6") (pinfunction "6_6") (pintype "passive"))
    )
    (net (code "23") (name "CD4021_CLK") (class "Default")
      (node (ref "U1") (pin "35") (pinfunction "GPIO28(ADC11)_35") (pintype "bidirectional"))
      (node (ref "U1") (pin "B35") (pinfunction "GPIO28(ADC11)_B35") (pintype "bidirectional"))
      (node (ref "U16") (pin "2A") (pinfunction "CD4021_CLK_2A") (pintype "bidirectional"))
    )
    (net (code "24") (name "CD4021_CS") (class "Default")
      (node (ref "U1") (pin "34") (pinfunction "GPIO27(SAI2_FS_B)_34") (pintype "bidirectional"))
      (node (ref "U1") (pin "B34") (pinfunction "GPIO27(SAI2_FS_B)_B34") (pintype "bidirectional"))
      (node (ref "U16") (pin "3A") (pinfunction "CD4021_CS_3A") (pintype "bidirectional"))
    )
    (net (code "25") (name "CD4021_D1") (class "Default")
      (node (ref "U1") (pin "33") (pinfunction "GPIO26(SAI2_SD_A)_33") (pintype "bidirectional"))
      (node (ref "U1") (pin "B33") (pinfunction "GPIO26(SAI2_SD_A)_B33") (pintype "bidirectional"))
      (node (ref "U16") (pin "1A") (pinfunction "CD4021_D1_1A") (pintype "bidirectional"))
    )
    (net (code "26") (name "CV_OUT_1") (class "Default")
      (node (ref "J_CV_OUT_1") (pin "3") (pinfunction "TIP_3") (pintype "passive"))
      (node (ref "R14") (pin "2") (pinfunction "2_2") (pintype "passive"))
    )
    (net (code "27") (name "CV_OUT_2") (class "Default")
      (node (ref "J_CV_OUT_2") (pin "3") (pinfunction "TIP_3") (pintype "passive"))
      (node (ref "R15") (pin "2") (pinfunction "2_2") (pintype "passive"))
    )
    (net (code "28") (name "DAC_OUT_1") (class "Default")
      (node (ref "U1") (pin "30") (pinfunction "GPIO23(ADC8/DAC1)_30") (pintype "bidirectional"))
      (node (ref "U1") (pin "B30") (pinfunction "GPIO23(ADC8/DAC1)_B30") (pintype "bidirectional"))
      (node (ref "U3") (pin "12") (pinfunction "+IN_12") (pintype "input"))
    )
    (net (code "29") (name "DAC_OUT_2") (class "Default")
      (node (ref "U1") (pin "29") (pinfunction "GPIO22(ADC7/DAC2)_29") (pintype "bidirectional"))
      (node (ref "U1") (pin "B29") (pinfunction "GPIO22(ADC7/DAC2)_B29") (pintype "bidirectional"))
      (node (ref "U3") (pin "5") (pinfunction "+IN_5") (pintype "input"))
    )
    (net (code "30") (name "GATE_IN") (class "Default")
      (node (ref "R30") (pin "1") (pinfunction "1_1") (pintype "passive"))
      (node (ref "U1") (pin "1") (pinfunction "GPIO0(USB_HS_ID)_1") (pintype "bidirectional"))
      (node (ref "U1") (pin "B1") (pinfunction "GPIO0(USB_HS_ID)_B1") (pintype "bidirectional"))
    )
    (net (code "31") (name "GATE_JACK_IN") (class "Default")
      (node (ref "J_GATE_IN_1") (pin "3") (pinfunction "TIP_3") (pintype "passive"))
      (node (ref "R22") (pin "1") (pinfunction "1_1") (pintype "passive"))
    )
    (net (code "32") (name "GATE_OUT") (class "Default")
      (node (ref "U1") (pin "22") (pinfunction "GPIO15(ADC0)_22") (pintype "bidirectional"))
      (node (ref "U1") (pin "B22") (pinfunction "GPIO15(ADC0)_B22") (pintype "bidirectional"))
      (node (ref "U3") (pin "10") (pinfunction "+IN_10") (pintype "input"))
    )
    (net (code "33") (name "GND") (class "Default")
      (node (ref "C1") (pin "1") (pinfunction "1_1") (pintype "passive"))
      (node (ref "C11") (pin "2") (pinfunction "2_2") (pintype "passive"))
      (node (ref "C13") (pin "2") (pinfunction "2_2") (pintype "passive"))
      (node (ref "C14") (pin "1") (pinfunction "1_1") (pintype "passive"))
      (node (ref "C15") (pin "1") (pinfunction "1_1") (pintype "passive"))
      (node (ref "C16") (pin "2") (pinfunction "2_2") (pintype "passive"))
      (node (ref "C17") (pin "2") (pinfunction "2_2") (pintype "passive"))
      (node (ref "C18") (pin "2") (pinfunction "2_2") (pintype "passive"))
      (node (ref "C2") (pin "2") (pinfunction "2_2") (pintype "passive"))
      (node (ref "C23") (pin "2") (pinfunction "2_2") (pintype "passive"))
      (node (ref "C3") (pin "2") (pinfunction "2_2") (pintype "passive"))
      (node (ref "C4") (pin "1") (pinfunction "1_1") (pintype "passive"))
      (node (ref "C5") (pin "2") (pinfunction "2_2") (pintype "passive"))
      (node (ref "C56") (pin "1") (pinfunction "1_1") (pintype "passive"))
      (node (ref "C59") (pin "2") (pinfunction "2_2") (pintype "passive"))
      (node (ref "C6") (pin "1") (pinfunction "1_1") (pintype "passive"))
      (node (ref "C60") (pin "1") (pinfunction "1_1") (pintype "passive"))
      (node (ref "C7") (pin "1") (pinfunction "1_1") (pintype "passive"))
      (node (ref "H3") (pin "B3,2") (pinfunction "MOUNT_B3,2") (pintype "passive"))
      (node (ref "J7") (pin "1") (pinfunction "GND_1") (pintype "passive"))
      (node (ref "J7") (pin "4") (pinfunction "GND_4") (pintype "passive"))
      (node (ref "J_CV_1") (pin "1") (pinfunction "GND_1") (pintype "passive"))
      (node (ref "J_CV_1") (pin "2") (pinfunction "NORM_2") (pintype "passive"))
      (node (ref "J_CV_2") (pin "1") (pinfunction "GND_1") (pintype "passive"))
      (node (ref "J_CV_2") (pin "2") (pinfunction "NORM_2") (pintype "passive"))
      (node (ref "J_CV_3") (pin "1") (pinfunction "GND_1") (pintype "passive"))
      (node (ref "J_CV_3") (pin "2") (pinfunction "NORM_2") (pintype "passive"))
      (node (ref "J_CV_4") (pin "1") (pinfunction "GND_1") (pintype "passive"))
      (node (ref "J_CV_4") (pin "2") (pinfunction "NORM_2") (pintype "passive"))
      (node (ref "J_CV_OUT_1") (pin "1") (pinfunction "GND_1") (pintype "passive"))
      (node (ref "J_CV_OUT_2") (pin "1") (pinfunction "GND_1") (pintype "passive"))
      (node (ref "J_GATE_IN_1") (pin "1") (pinfunction "GND_1") (pintype "passive"))
      (node (ref "J_GATE_OUT") (pin "1") (pinfunction "GND_1") (pintype "passive"))
      (node (ref "J_MIDI_IN") (pin "GND") (pinfunction "GND_GND") (pintype "passive"))
      (node (ref "J_MIDI_OUT") (pin "GND") (pinfunction "GND_GND") (pintype "passive"))
      (node (ref "P1") (pin "13") (pinfunction "13_13") (pintype "passive"))
      (node (ref "P1") (pin "14") (pinfunction "14_14") (pintype "passive"))
      (node (ref "P1") (pin "15") (pinfunction "15_15") (pintype "passive"))
      (node (ref "P1") (pin "16") (pinfunction "16_16") (pintype "passive"))
      (node (ref "P1") (pin "3") (pinfunction "3_3") (pintype "passive"))
      (node (ref "P1") (pin "4") (pinfunction "4_4") (pintype "passive"))
      (node (ref "Q1") (pin "E") (pinfunction "E_E") (pintype "passive"))
      (node (ref "R11") (pin "1") (pinfunction "1_1") (pintype "passive"))
      (node (ref "R18") (pin "1") (pinfunction "1_1") (pintype "passive"))
      (node (ref "R28") (pin "1") (pinfunction "1_1") (pintype "passive"))
      (node (ref "R35") (pin "2") (pinfunction "2_2") (pintype "passive"))
      (node (ref "R38") (pin "1") (pinfunction "1_1") (pintype "passive"))
      (node (ref "R40") (pin "1") (pinfunction "1_1") (pintype "passive"))
      (node (ref "R46") (pin "1") (pinfunction "1_1") (pintype "passive"))
      (node (ref "R47") (pin "1") (pinfunction "1_1") (pintype "passive"))
      (node (ref "R49") (pin "2") (pinfunction "2_2") (pintype "passive"))
      (node (ref "R53") (pin "1") (pinfunction "1_1") (pintype "passive"))
      (node (ref "R57") (pin "2") (pinfunction "2_2") (pintype "passive"))
      (node (ref "R61") (pin "2") (pinfunction "2_2") (pintype "passive"))
      (node (ref "R65") (pin "1") (pinfunction "1_1") (pintype "passive"))
      (node (ref "R66") (pin "1") (pinfunction "1_1") (pintype "passive"))
      (node (ref "R88") (pin "1") (pinfunction "1_1") (pintype "passive"))
      (node (ref "R9") (pin "1") (pinfunction "1_1") (pintype "passive"))
      (node (ref "S1") (pin "3") (pinfunction "3_3") (pintype "passive"))
      (node (ref "S1") (pin "4") (pinfunction "4_4") (pintype "passive"))
      (node (ref "S2") (pin "3") (pinfunction "3_3") (pintype "passive"))
      (node (ref "S2") (pin "4") (pinfunction "4_4") (pintype "passive"))
      (node (ref "U$4") (pin "P$1") (pinfunction "IN-_P$1") (pintype "bidirectional"))
      (node (ref "U$4") (pin "P$4") (pinfunction "OUT-_P$4") (pintype "bidirectional"))
      (node (ref "U1") (pin "20") (pinfunction "AGND_20") (pintype "bidirectional"))
      (node (ref "U1") (pin "40") (pinfunction "GND_40") (pintype "bidirectional"))
      (node (ref "U1") (pin "B20") (pinfunction "AGND_B20") (pintype "bidirectional"))
      (node (ref "U1") (pin "B40") (pinfunction "GND_B40") (pintype "bidirectional"))
      (node (ref "U10") (pin "11") (pinfunction "V-_11") (pintype "power_in"))
      (node (ref "U11") (pin "6") (pinfunction "INH_6") (pintype "input"))
      (node (ref "U11") (pin "7") (pinfunction "VEE_7") (pintype "power_in"))
      (node (ref "U11") (pin "8") (pinfunction "GND_8") (pintype "power_in"))
      (node (ref "U15") (pin "5") (pinfunction "GND_5") (pintype "bidirectional"))
      (node (ref "U16") (pin "6A") (pinfunction "GND_6A") (pintype "bidirectional"))
      (node (ref "U2") (pin "GND1") (pinfunction "SHIELD_GND1") (pintype "bidirectional"))
      (node (ref "U2") (pin "GND2") (pinfunction "SHIELD_GND2") (pintype "bidirectional"))
      (node (ref "U2") (pin "P$6") (pinfunction "GND_P$6") (pintype "bidirectional"))
      (node (ref "U3") (pin "11") (pinfunction "V-_11") (pintype "power_in"))
      (node (ref "U4") (pin "2") (pinfunction "GND_2") (pintype "bidirectional"))
      (node (ref "U4") (pin "3") (pinfunction "SDOWN_3") (pintype "bidirectional"))
      (node (ref "U4") (pin "9") (pinfunction "GND_9") (pintype "bidirectional"))
      (node (ref "U5") (pin "1") (pinfunction "A0_1") (pintype "bidirectional"))
      (node (ref "U5") (pin "14") (pinfunction "GND_14") (pintype "power_in"))
      (node (ref "U5") (pin "23") (pinfunction "/OE_23") (pintype "bidirectional"))
      (node (ref "U5") (pin "24") (pinfunction "A5_24") (pintype "bidirectional"))
      (node (ref "U5") (pin "25") (pinfunction "EXTCLK_25") (pintype "input"))
      (node (ref "U5") (pin "3") (pinfunction "A2_3") (pintype "bidirectional"))
      (node (ref "U5") (pin "4") (pinfunction "A3_4") (pintype "bidirectional"))
      (node (ref "U5") (pin "5") (pinfunction "A4_5") (pintype "bidirectional"))
      (node (ref "U6") (pin "11") (pinfunction "V-_11") (pintype "power_in"))
      (node (ref "U7") (pin "1") (pinfunction "PGND_1") (pintype "bidirectional"))
      (node (ref "U7") (pin "4") (pinfunction "AGND_4") (pintype "bidirectional"))
      (node (ref "U7") (pin "P$1") (pinfunction "PAD_P$1") (pintype "bidirectional"))
      (node (ref "U7") (pin "P$9") (pinfunction "PAD_P$9") (pintype "bidirectional"))
      (node (ref "U8") (pin "1") (pinfunction "GND_1") (pintype "bidirectional"))
      (node (ref "U9") (pin "1") (pinfunction "GND_1") (pintype "input"))
      (node (ref "VR1") (pin "1") (pinfunction "1_1") (pintype "passive"))
      (node (ref "VR1") (pin "1P") (pinfunction "1_1P") (pintype "passive"))
      (node (ref "VR_1") (pin "1") (pinfunction "1_1") (pintype "passive"))
      (node (ref "VR_2") (pin "1") (pinfunction "1_1") (pintype "passive"))
      (node (ref "VR_3") (pin "1") (pinfunction "1_1") (pintype "passive"))
      (node (ref "VR_4") (pin "1") (pinfunction "1_1") (pintype "passive"))
      (node (ref "VR_5") (pin "1") (pinfunction "1_1") (pintype "passive"))
      (node (ref "VR_6") (pin "1") (pinfunction "1_1") (pintype "passive"))
      (node (ref "VR_7") (pin "1") (pinfunction "1_1") (pintype "passive"))
      (node (ref "VR_8") (pin "1") (pinfunction "A_1") (pintype "passive"))
      (node (ref "VR_8") (pin "CHASSIS1") (pinfunction "CHASSIS_CHASSIS1") (pintype "passive"))
      (node (ref "VR_8") (pin "CHASSIS2") (pinfunction "CHASSIS_CHASSIS2") (pintype "passive"))
    )
    (net (code "34") (name "GND_2") (class "Default")
      (node (ref "J10") (pin "1") (pinfunction "SLEEVE_1") (pintype "passive"))
      (node (ref "J10") (pin "4") (pinfunction "SLEEVE_SW_4") (pintype "passive"))
      (node (ref "J12") (pin "1") (pinfunction "SLEEVE_1") (pintype "passive"))
      (node (ref "J12") (pin "4") (pinfunction "SLEEVE_SW_4") (pintype "passive"))
      (node (ref "J13") (pin "1") (pinfunction "SLEEVE_1") (pintype "passive"))
      (node (ref "J13") (pin "4") (pinfunction "SLEEVE_SW_4") (pintype "passive"))
      (node (ref "J8") (pin "1") (pinfunction "SLEEVE_1") (pintype "passive"))
      (node (ref "J8") (pin "4") (pinfunction "SLEEVE_SW_4") (pintype "passive"))
      (node (ref "J9") (pin "1") (pinfunction "SLEEVE_1") (pintype "passive"))
      (node (ref "J9") (pin "4") (pinfunction "SLEEVE_SW_4") (pintype "passive"))
      (node (ref "P2") (pin "13") (pinfunction "13_13") (pintype "passive"))
      (node (ref "P2") (pin "14") (pinfunction "14_14") (pintype "passive"))
      (node (ref "P2") (pin "15") (pinfunction "15_15") (pintype "passive"))
      (node (ref "P2") (pin "16") (pinfunction "16_16") (pintype "passive"))
      (node (ref "P2") (pin "3") (pinfunction "3_3") (pintype "passive"))
      (node (ref "P2") (pin "4") (pinfunction "4_4") (pintype "passive"))
    )
    (net (code "35") (name "HEADPHONE_OUT_L") (class "Default")
      (node (ref "C62") (pin "-") (pinfunction "NEG_-") (pintype "passive"))
      (node (ref "P1") (pin "2") (pinfunction "2_2") (pintype "passive"))
    )
    (net (code "36") (name "HEADPHONE_OUT_R") (class "Default")
      (node (ref "C63") (pin "-") (pinfunction "NEG_-") (pintype "passive"))
      (node (ref "P1") (pin "1") (pinfunction "1_1") (pintype "passive"))
    )
    (net (code "37") (name "HEADPHONE_WIPER_L") (class "Default")
      (node (ref "C53") (pin "1") (pinfunction "1_1") (pintype "passive"))
      (node (ref "R7") (pin "2") (pinfunction "2_2") (pintype "passive"))
      (node (ref "VR1") (pin "2P") (pinfunction "2_2P") (pintype "passive"))
    )
    (net (code "38") (name "HEADPHONE_WIPER_R") (class "Default")
      (node (ref "C54") (pin "1") (pinfunction "1_1") (pintype "passive"))
      (node (ref "R20") (pin "2") (pinfunction "2_2") (pintype "passive"))
      (node (ref "VR1") (pin "2") (pinfunction "2_2") (pintype "passive"))
    )
    (net (code "39") (name "HP_OUT_L_EXT") (class "Default")
      (node (ref "J10") (pin "2") (pinfunction "TIP_2") (pintype "passive"))
      (node (ref "P2") (pin "2") (pinfunction "2_2") (pintype "passive"))
    )
    (net (code "40") (name "HP_OUT_R_EXT") (class "Default")
      (node (ref "J10") (pin "3") (pinfunction "RING_3") (pintype "passive"))
      (node (ref "P2") (pin "1") (pinfunction "1_1") (pintype "passive"))
    )
    (net (code "41") (name "I2C1_SCL") (class "Default")
      (node (ref "R73") (pin "2") (pinfunction "2_2") (pintype "passive"))
      (node (ref "U1") (pin "12") (pinfunction "GPIO11(I2C1_SCL)_12") (pintype "bidirectional"))
      (node (ref "U1") (pin "B12") (pinfunction "GPIO11(I2C1_SCL)_B12") (pintype "bidirectional"))
      (node (ref "U16") (pin "5A") (pinfunction "I2C_SCL_5A") (pintype "bidirectional"))
      (node (ref "U5") (pin "26") (pinfunction "SCL_26") (pintype "bidirectional"))
    )
    (net (code "42") (name "I2C1_SDA") (class "Default")
      (node (ref "R72") (pin "2") (pinfunction "2_2") (pintype "passive"))
      (node (ref "U1") (pin "13") (pinfunction "GPIO12(I2C1_SDA)_13") (pintype "bidirectional"))
      (node (ref "U1") (pin "B13") (pinfunction "GPIO12(I2C1_SDA)_B13") (pintype "bidirectional"))
      (node (ref "U16") (pin "4A") (pinfunction "I2C_SDA_4A") (pintype "bidirectional"))
      (node (ref "U5") (pin "27") (pinfunction "SDA_27") (pintype "bidirectional"))
    )
    (net (code "43") (name "LED_KNOB_1_G") (class "Default")
      (node (ref "R6") (pin "1") (pinfunction "1_1") (pintype "passive"))
      (node (ref "U5") (pin "6") (pinfunction "LED0_6") (pintype "bidirectional"))
    )
    (net (code "44") (name "LED_KNOB_2_G") (class "Default")
      (node (ref "R12") (pin "1") (pinfunction "1_1") (pintype "passive"))
      (node (ref "U5") (pin "7") (pinfunction "LED1_7") (pintype "bidirectional"))
    )
    (net (code "45") (name "LED_KNOB_3_G") (class "Default")
      (node (ref "R19") (pin "1") (pinfunction "1_1") (pintype "passive"))
      (node (ref "U5") (pin "8") (pinfunction "LED2_8") (pintype "bidirectional"))
    )
    (net (code "46") (name "LED_KNOB_4_G") (class "Default")
      (node (ref "R25") (pin "1") (pinfunction "1_1") (pintype "passive"))
      (node (ref "U5") (pin "9") (pinfunction "LED3_9") (pintype "bidirectional"))
    )
    (net (code "47") (name "LED_KNOB_5_G") (class "Default")
      (node (ref "R31") (pin "1") (pinfunction "1_1") (pintype "passive"))
      (node (ref "U5") (pin "10") (pinfunction "LED4_10") (pintype "bidirectional"))
    )
    (net (code "48") (name "LED_KNOB_6_G") (class "Default")
      (node (ref "R37") (pin "1") (pinfunction "1_1") (pintype "passive"))
      (node (ref "U5") (pin "11") (pinfunction "LED5_11") (pintype "bidirectional"))
    )
    (net (code "49") (name "LED_KNOB_7_G") (class "Default")
      (node (ref "R43") (pin "1") (pinfunction "1_1") (pintype "passive"))
      (node (ref "U5") (pin "12") (pinfunction "LED6_12") (pintype "bidirectional"))
    )
    (net (code "50") (name "LED_KNOB_8_G") (class "Default")
      (node (ref "R52") (pin "1") (pinfunction "1_1") (pintype "passive"))
      (node (ref "U5") (pin "13") (pinfunction "LED7_13") (pintype "bidirectional"))
    )
    (net (code "51") (name "MIDI_IN_A") (class "Default")
      (node (ref "R63") (pin "2") (pinfunction "2_2") (pintype "passive"))
      (node (ref "R78") (pin "1") (pinfunction "1_1") (pintype "passive"))
      (node (ref "R79") (pin "1") (pinfunction "1_1") (pintype "passive"))
    )
    (net (code "52") (name "MIDI_IN_B") (class "Default")
      (node (ref "D5") (pin "A") (pinfunction "A_A") (pintype "passive"))
      (node (ref "R83") (pin "1") (pinfunction "1_1") (pintype "passive"))
      (node (ref "R84") (pin "1") (pinfunction "1_1") (pintype "passive"))
      (node (ref "U15") (pin "2") (pinfunction "C_2") (pintype "bidirectional"))
    )
    (net (code "53") (name "MIDI_IN_RING") (class "Default")
      (node (ref "J_MIDI_IN") (pin "RING") (pinfunction "NORM_RING") (pintype "passive"))
      (node (ref "R79") (pin "2") (pinfunction "2_2") (pintype "passive"))
      (node (ref "R84") (pin "2") (pinfunction "2_2") (pintype "passive"))
    )
    (net (code "54") (name "MIDI_IN_TIP") (class "Default")
      (node (ref "J_MIDI_IN") (pin "TIP") (pinfunction "TIP_TIP") (pintype "passive"))
      (node (ref "R78") (pin "2") (pinfunction "2_2") (pintype "passive"))
      (node (ref "R83") (pin "2") (pinfunction "2_2") (pintype "passive"))
    )
    (net (code "55") (name "MUX_SEL_0") (class "Default")
      (node (ref "U1") (pin "28") (pinfunction "GPIO21(ADC6)_28") (pintype "bidirectional"))
      (node (ref "U1") (pin "B28") (pinfunction "GPIO21(ADC6)_B28") (pintype "bidirectional"))
      (node (ref "U11") (pin "11") (pinfunction "A_11") (pintype "input"))
    )
    (net (code "56") (name "MUX_SEL_1") (class "Default")
      (node (ref "U1") (pin "27") (pinfunction "GPIO20(ADC5)_27") (pintype "bidirectional"))
      (node (ref "U1") (pin "B27") (pinfunction "GPIO20(ADC5)_B27") (pintype "bidirectional"))
      (node (ref "U11") (pin "10") (pinfunction "B_10") (pintype "input"))
    )
    (net (code "57") (name "MUX_SEL_2") (class "Default")
      (node (ref "U1") (pin "26") (pinfunction "GPIO19(ADC4)_26") (pintype "bidirectional"))
      (node (ref "U1") (pin "B26") (pinfunction "GPIO19(ADC4)_B26") (pintype "bidirectional"))
      (node (ref "U11") (pin "9") (pinfunction "C_9") (pintype "input"))
    )
    (net (code "58") (name "Net-(C20-Pad1)") (class "Default")
      (node (ref "C20") (pin "1") (pinfunction "1_1") (pintype "passive"))
      (node (ref "R69") (pin "1") (pinfunction "1_1") (pintype "passive"))
    )
    (net (code "59") (name "Net-(C22-Pad1)") (class "Default")
      (node (ref "C22") (pin "1") (pinfunction "1_1") (pintype "passive"))
      (node (ref "R71") (pin "1") (pinfunction "1_1") (pintype "passive"))
    )
    (net (code "60") (name "Net-(C53-Pad2)") (class "Default")
      (node (ref "C53") (pin "2") (pinfunction "2_2") (pintype "passive"))
      (node (ref "R23") (pin "2") (pinfunction "2_2") (pintype "passive"))
    )
    (net (code "61") (name "Net-(C54-Pad2)") (class "Default")
      (node (ref "C54") (pin "2") (pinfunction "2_2") (pintype "passive"))
      (node (ref "R24") (pin "2") (pinfunction "2_2") (pintype "passive"))
    )
    (net (code "62") (name "Net-(C62-POS)") (class "Default")
      (node (ref "C62") (pin "+") (pinfunction "POS_+") (pintype "passive"))
      (node (ref "R27") (pin "1") (pinfunction "1_1") (pintype "passive"))
      (node (ref "U4") (pin "7") (pinfunction "OUT1_7") (pintype "bidirectional"))
    )
    (net (code "63") (name "Net-(C63-POS)") (class "Default")
      (node (ref "C63") (pin "+") (pinfunction "POS_+") (pintype "passive"))
      (node (ref "R33") (pin "1") (pinfunction "1_1") (pintype "passive"))
      (node (ref "U4") (pin "5") (pinfunction "OUT2_5") (pintype "bidirectional"))
    )
    (net (code "64") (name "Net-(J7-PIN)") (class "Default")
      (node (ref "D1") (pin "A") (pinfunction "A_A") (pintype "passive"))
      (node (ref "J7") (pin "3") (pinfunction "PIN_3") (pintype "passive"))
    )
    (net (code "65") (name "Net-(J_CV_1-TIP)") (class "Default")
      (node (ref "J_CV_1") (pin "3") (pinfunction "TIP_3") (pintype "passive"))
      (node (ref "R70") (pin "1") (pinfunction "1_1") (pintype "passive"))
    )
    (net (code "66") (name "Net-(J_CV_2-TIP)") (class "Default")
      (node (ref "J_CV_2") (pin "3") (pinfunction "TIP_3") (pintype "passive"))
      (node (ref "R41") (pin "1") (pinfunction "1_1") (pintype "passive"))
    )
    (net (code "67") (name "Net-(J_CV_3-TIP)") (class "Default")
      (node (ref "J_CV_3") (pin "3") (pinfunction "TIP_3") (pintype "passive"))
      (node (ref "R51") (pin "1") (pinfunction "1_1") (pintype "passive"))
    )
    (net (code "68") (name "Net-(J_CV_4-TIP)") (class "Default")
      (node (ref "J_CV_4") (pin "3") (pinfunction "TIP_3") (pintype "passive"))
      (node (ref "R59") (pin "1") (pinfunction "1_1") (pintype "passive"))
    )
    (net (code "69") (name "Net-(J_GATE_OUT-TIP)") (class "Default")
      (node (ref "J_GATE_OUT") (pin "3") (pinfunction "TIP_3") (pintype "passive"))
      (node (ref "R21") (pin "2") (pinfunction "2_2") (pintype "passive"))
    )
    (net (code "70") (name "Net-(J_MIDI_OUT-NORM)") (class "Default")
      (node (ref "J_MIDI_OUT") (pin "RING") (pinfunction "NORM_RING") (pintype "passive"))
      (node (ref "R54") (pin "2") (pinfunction "2_2") (pintype "passive"))
    )
    (net (code "71") (name "Net-(J_MIDI_OUT-PadTIP)") (class "Default")
      (node (ref "J_MIDI_OUT") (pin "TIP") (pinfunction "TIP_TIP") (pintype "passive"))
      (node (ref "R55") (pin "1") (pinfunction "1_1") (pintype "passive"))
    )
    (net (code "72") (name "Net-(LED_KNOBG1-C)") (class "Default")
      (node (ref "LED_KNOBG1") (pin "CATHODE") (pinfunction "C_CATHODE") (pintype "passive"))
      (node (ref "R6") (pin "2") (pinfunction "2_2") (pintype "passive"))
    )
    (net (code "73") (name "Net-(LED_KNOBG2-C)") (class "Default")
      (node (ref "LED_KNOBG2") (pin "CATHODE") (pinfunction "C_CATHODE") (pintype "passive"))
      (node (ref "R12") (pin "2") (pinfunction "2_2") (pintype "passive"))
    )
    (net (code "74") (name "Net-(LED_KNOBG3-C)") (class "Default")
      (node (ref "LED_KNOBG3") (pin "CATHODE") (pinfunction "C_CATHODE") (pintype "passive"))
      (node (ref "R19") (pin "2") (pinfunction "2_2") (pintype "passive"))
    )
    (net (code "75") (name "Net-(LED_KNOBG4-C)") (class "Default")
      (node (ref "LED_KNOBG4") (pin "CATHODE") (pinfunction "C_CATHODE") (pintype "passive"))
      (node (ref "R25") (pin "2") (pinfunction "2_2") (pintype "passive"))
    )
    (net (code "76") (name "Net-(LED_KNOBG5-C)") (class "Default")
      (node (ref "LED_KNOBG5") (pin "CATHODE") (pinfunction "C_CATHODE") (pintype "passive"))
      (node (ref "R31") (pin "2") (pinfunction "2_2") (pintype "passive"))
    )
    (net (code "77") (name "Net-(LED_KNOBG6-C)") (class "Default")
      (node (ref "LED_KNOBG6") (pin "CATHODE") (pinfunction "C_CATHODE") (pintype "passive"))
      (node (ref "R37") (pin "2") (pinfunction "2_2") (pintype "passive"))
    )
    (net (code "78") (name "Net-(LED_KNOBG7-C)") (class "Default")
      (node (ref "LED_KNOBG7") (pin "CATHODE") (pinfunction "C_CATHODE") (pintype "passive"))
      (node (ref "R43") (pin "2") (pinfunction "2_2") (pintype "passive"))
    )
    (net (code "79") (name "Net-(LED_KNOBG8-C)") (class "Default")
      (node (ref "LED_KNOBG8") (pin "CATHODE") (pinfunction "C_CATHODE") (pintype "passive"))
      (node (ref "R52") (pin "2") (pinfunction "2_2") (pintype "passive"))
    )
    (net (code "80") (name "Net-(Q1-PadB)") (class "Default")
      (node (ref "Q1") (pin "B") (pinfunction "B_B") (pintype "passive"))
      (node (ref "R22") (pin "2") (pinfunction "2_2") (pintype "passive"))
      (node (ref "R28") (pin "2") (pinfunction "2_2") (pintype "passive"))
    )
    (net (code "81") (name "Net-(Q1-PadC)") (class "Default")
      (node (ref "Q1") (pin "C") (pinfunction "C_C") (pintype "passive"))
      (node (ref "R29") (pin "1") (pinfunction "1_1") (pintype "passive"))
      (node (ref "R30") (pin "2") (pinfunction "2_2") (pintype "passive"))
    )
    (net (code "82") (name "Net-(U$4-IN+)") (class "Default")
      (node (ref "C17") (pin "1") (pinfunction "1_1") (pintype "passive"))
      (node (ref "L1") (pin "P$2") (pinfunction "P$2_P$2") (pintype "bidirectional"))
      (node (ref "U$4") (pin "P$2") (pinfunction "IN+_P$2") (pintype "bidirectional"))
    )
    (net (code "83") (name "Net-(U3A-+IN)") (class "Default")
      (node (ref "R66") (pin "2") (pinfunction "2_2") (pintype "passive"))
      (node (ref "R67") (pin "1") (pinfunction "1_1") (pintype "passive"))
      (node (ref "U3") (pin "3") (pinfunction "+IN_3") (pintype "input"))
    )
    (net (code "84") (name "Net-(U3B--IN)") (class "Default")
      (node (ref "R10") (pin "1") (pinfunction "1_1") (pintype "passive"))
      (node (ref "R11") (pin "2") (pinfunction "2_2") (pintype "passive"))
      (node (ref "U3") (pin "6") (pinfunction "-IN_6") (pintype "input"))
    )
    (net (code "85") (name "Net-(U3B-OUT)") (class "Default")
      (node (ref "R10") (pin "2") (pinfunction "2_2") (pintype "passive"))
      (node (ref "R15") (pin "1") (pinfunction "1_1") (pintype "passive"))
      (node (ref "U3") (pin "7") (pinfunction "OUT_7") (pintype "output"))
    )
    (net (code "86") (name "Net-(U3C--IN)") (class "Default")
      (node (ref "R17") (pin "1") (pinfunction "1_1") (pintype "passive"))
      (node (ref "R18") (pin "2") (pinfunction "2_2") (pintype "passive"))
      (node (ref "U3") (pin "9") (pinfunction "-IN_9") (pintype "input"))
    )
    (net (code "87") (name "Net-(U3C-OUT)") (class "Default")
      (node (ref "R17") (pin "2") (pinfunction "2_2") (pintype "passive"))
      (node (ref "R21") (pin "1") (pinfunction "1_1") (pintype "passive"))
      (node (ref "U3") (pin "8") (pinfunction "OUT_8") (pintype "output"))
    )
    (net (code "88") (name "Net-(U3D--IN)") (class "Default")
      (node (ref "R8") (pin "1") (pinfunction "1_1") (pintype "passive"))
      (node (ref "R9") (pin "2") (pinfunction "2_2") (pintype "passive"))
      (node (ref "U3") (pin "13") (pinfunction "-IN_13") (pintype "input"))
    )
    (net (code "89") (name "Net-(U3D-OUT)") (class "Default")
      (node (ref "R14") (pin "1") (pinfunction "1_1") (pintype "passive"))
      (node (ref "R8") (pin "2") (pinfunction "2_2") (pintype "passive"))
      (node (ref "U3") (pin "14") (pinfunction "OUT_14") (pintype "output"))
    )
    (net (code "90") (name "Net-(U4-BPASS)") (class "Default")
      (node (ref "C56") (pin "2") (pinfunction "2_2") (pintype "passive"))
      (node (ref "U4") (pin "1") (pinfunction "BPASS_1") (pintype "bidirectional"))
    )
    (net (code "91") (name "Net-(U4-IN1)") (class "Default")
      (node (ref "R23") (pin "1") (pinfunction "1_1") (pintype "passive"))
      (node (ref "R27") (pin "2") (pinfunction "2_2") (pintype "passive"))
      (node (ref "U4") (pin "8") (pinfunction "IN1_8") (pintype "bidirectional"))
    )
    (net (code "92") (name "Net-(U4-IN2)") (class "Default")
      (node (ref "R24") (pin "1") (pinfunction "1_1") (pintype "passive"))
      (node (ref "R33") (pin "2") (pinfunction "2_2") (pintype "passive"))
      (node (ref "U4") (pin "4") (pinfunction "IN2_4") (pintype "bidirectional"))
    )
    (net (code "93") (name "Net-(U6A-+IN)") (class "Default")
      (node (ref "R42") (pin "1") (pinfunction "1_1") (pintype "passive"))
      (node (ref "R49") (pin "1") (pinfunction "1_1") (pintype "passive"))
      (node (ref "U6") (pin "3") (pinfunction "+IN_3") (pintype "input"))
    )
    (net (code "94") (name "Net-(U6A--IN)") (class "Default")
      (node (ref "C8") (pin "1") (pinfunction "1_1") (pintype "passive"))
      (node (ref "R36") (pin "1") (pinfunction "1_1") (pintype "passive"))
      (node (ref "R41") (pin "2") (pinfunction "2_2") (pintype "passive"))
      (node (ref "U6") (pin "2") (pinfunction "-IN_2") (pintype "input"))
    )
    (net (code "95") (name "Net-(U6B-+IN)") (class "Default")
      (node (ref "R56") (pin "1") (pinfunction "1_1") (pintype "passive"))
      (node (ref "R57") (pin "1") (pinfunction "1_1") (pintype "passive"))
      (node (ref "U6") (pin "5") (pinfunction "+IN_5") (pintype "input"))
    )
    (net (code "96") (name "Net-(U6B--IN)") (class "Default")
      (node (ref "C10") (pin "1") (pinfunction "1_1") (pintype "passive"))
      (node (ref "R50") (pin "1") (pinfunction "1_1") (pintype "passive"))
      (node (ref "R51") (pin "2") (pinfunction "2_2") (pintype "passive"))
      (node (ref "U6") (pin "6") (pinfunction "-IN_6") (pintype "input"))
    )
    (net (code "97") (name "Net-(U6C-+IN)") (class "Default")
      (node (ref "R60") (pin "1") (pinfunction "1_1") (pintype "passive"))
      (node (ref "R61") (pin "1") (pinfunction "1_1") (pintype "passive"))
      (node (ref "U6") (pin "10") (pinfunction "+IN_10") (pintype "input"))
    )
    (net (code "98") (name "Net-(U6C--IN)") (class "Default")
      (node (ref "C12") (pin "1") (pinfunction "1_1") (pintype "passive"))
      (node (ref "R58") (pin "1") (pinfunction "1_1") (pintype "passive"))
      (node (ref "R59") (pin "2") (pinfunction "2_2") (pintype "passive"))
      (node (ref "U6") (pin "9") (pinfunction "-IN_9") (pintype "input"))
    )
    (net (code "99") (name "Net-(U6D-+IN)") (class "Default")
      (node (ref "R34") (pin "1") (pinfunction "1_1") (pintype "passive"))
      (node (ref "R35") (pin "1") (pinfunction "1_1") (pintype "passive"))
      (node (ref "U6") (pin "12") (pinfunction "+IN_12") (pintype "input"))
    )
    (net (code "100") (name "Net-(U6D--IN)") (class "Default")
      (node (ref "C9") (pin "1") (pinfunction "1_1") (pintype "passive"))
      (node (ref "R68") (pin "1") (pinfunction "1_1") (pintype "passive"))
      (node (ref "R70") (pin "2") (pinfunction "2_2") (pintype "passive"))
      (node (ref "U6") (pin "13") (pinfunction "-IN_13") (pintype "input"))
    )
    (net (code "101") (name "Net-(U7-EN)") (class "Default")
      (node (ref "C59") (pin "1") (pinfunction "1_1") (pintype "passive"))
      (node (ref "FB4") (pin "2") (pinfunction "2_2") (pintype "passive"))
      (node (ref "U7") (pin "2") (pinfunction "VIN_2") (pintype "bidirectional"))
      (node (ref "U7") (pin "3") (pinfunction "EN_3") (pintype "bidirectional"))
    )
    (net (code "102") (name "Net-(U7-FB)") (class "Default")
      (node (ref "R87") (pin "1") (pinfunction "1_1") (pintype "passive"))
      (node (ref "R88") (pin "2") (pinfunction "2_2") (pintype "passive"))
      (node (ref "U7") (pin "5") (pinfunction "FB_5") (pintype "bidirectional"))
    )
    (net (code "103") (name "Net-(U7-SW)") (class "Default")
      (node (ref "L4") (pin "P$1") (pinfunction "P$1_P$1") (pintype "bidirectional"))
      (node (ref "U7") (pin "7") (pinfunction "SW_7") (pintype "bidirectional"))
    )
    (net (code "104") (name "Net-(U10A-+IN)") (class "Default")
      (node (ref "C19") (pin "2") (pinfunction "2_2") (pintype "passive"))
      (node (ref "R32") (pin "1") (pinfunction "1_1") (pintype "passive"))
      (node (ref "R38") (pin "2") (pinfunction "2_2") (pintype "passive"))
      (node (ref "U10") (pin "3") (pinfunction "+IN_3") (pintype "input"))
    )
    (net (code "105") (name "Net-(U10A--IN)") (class "Default")
      (node (ref "R69") (pin "2") (pinfunction "2_2") (pintype "passive"))
      (node (ref "U10") (pin "1") (pinfunction "OUT_1") (pintype "output"))
      (node (ref "U10") (pin "2") (pinfunction "-IN_2") (pintype "input"))
    )
    (net (code "106") (name "Net-(U10B-+IN)") (class "Default")
      (node (ref "C21") (pin "2") (pinfunction "2_2") (pintype "passive"))
      (node (ref "R44") (pin "1") (pinfunction "1_1") (pintype "passive"))
      (node (ref "R46") (pin "2") (pinfunction "2_2") (pintype "passive"))
      (node (ref "U10") (pin "5") (pinfunction "+IN_5") (pintype "input"))
    )
    (net (code "107") (name "Net-(U10B--IN)") (class "Default")
      (node (ref "R71") (pin "2") (pinfunction "2_2") (pintype "passive"))
      (node (ref "U10") (pin "6") (pinfunction "-IN_6") (pintype "input"))
      (node (ref "U10") (pin "7") (pinfunction "OUT_7") (pintype "output"))
    )
    (net (code "108") (name "Net-(U10C-+IN)") (class "Default")
      (node (ref "C24") (pin "2") (pinfunction "2_2") (pintype "passive"))
      (node (ref "R48") (pin "1") (pinfunction "1_1") (pintype "passive"))
      (node (ref "U10") (pin "10") (pinfunction "+IN_10") (pintype "input"))
    )
    (net (code "109") (name "Net-(U10D-+IN)") (class "Default")
      (node (ref "C25") (pin "2") (pinfunction "2_2") (pintype "passive"))
      (node (ref "R62") (pin "1") (pinfunction "1_1") (pintype "passive"))
      (node (ref "U10") (pin "12") (pinfunction "+IN_12") (pintype "input"))
    )
    (net (code "110") (name "Net-(U15-A)") (class "Default")
      (node (ref "D5") (pin "C") (pinfunction "C_C") (pintype "passive"))
      (node (ref "R63") (pin "1") (pinfunction "1_1") (pintype "passive"))
      (node (ref "U15") (pin "1") (pinfunction "A_1") (pintype "bidirectional"))
    )
    (net (code "111") (name "OLED_CMD") (class "Default")
      (node (ref "U1") (pin "10") (pinfunction "GPIO9(SPI1_MISO)_10") (pintype "bidirectional"))
      (node (ref "U1") (pin "B10") (pinfunction "GPIO9(SPI1_MISO)_B10") (pintype "bidirectional"))
      (node (ref "U8") (pin "6") (pinfunction "DC_6") (pintype "bidirectional"))
    )
    (net (code "112") (name "OLED_RESET") (class "Default")
      (node (ref "C15") (pin "2") (pinfunction "2_2") (pintype "passive"))
      (node (ref "R26") (pin "1") (pinfunction "1_1") (pintype "passive"))
      (node (ref "U8") (pin "5") (pinfunction "RES_5") (pintype "bidirectional"))
    )
    (net (code "113") (name "OUT_L_ATTEN") (class "Default")
      (node (ref "P1") (pin "7") (pinfunction "7_7") (pintype "passive"))
      (node (ref "P1") (pin "8") (pinfunction "8_8") (pintype "passive"))
      (node (ref "R5") (pin "1") (pinfunction "1_1") (pintype "passive"))
      (node (ref "R7") (pin "1") (pinfunction "1_1") (pintype "passive"))
    )
    (net (code "114") (name "OUT_R_ATTEN") (class "Default")
      (node (ref "P1") (pin "5") (pinfunction "5_5") (pintype "passive"))
      (node (ref "P1") (pin "6") (pinfunction "6_6") (pintype "passive"))
      (node (ref "R13") (pin "1") (pinfunction "1_1") (pintype "passive"))
      (node (ref "R20") (pin "1") (pinfunction "1_1") (pintype "passive"))
    )
    (net (code "115") (name "POT_1") (class "Default")
      (node (ref "U11") (pin "13") (pinfunction "X0_13") (pintype "bidirectional"))
      (node (ref "VR_1") (pin "2") (pinfunction "2_2") (pintype "passive"))
    )
    (net (code "116") (name "POT_2") (class "Default")
      (node (ref "U11") (pin "14") (pinfunction "X1_14") (pintype "bidirectional"))
      (node (ref "VR_3") (pin "2") (pinfunction "2_2") (pintype "passive"))
    )
    (net (code "117") (name "POT_3") (class "Default")
      (node (ref "U11") (pin "15") (pinfunction "X2_15") (pintype "bidirectional"))
      (node (ref "VR_5") (pin "2") (pinfunction "2_2") (pintype "passive"))
    )
    (net (code "118") (name "POT_4") (class "Default")
      (node (ref "U11") (pin "12") (pinfunction "X3_12") (pintype "bidirectional"))
      (node (ref "VR_2") (pin "2") (pinfunction "2_2") (pintype "passive"))
    )
    (net (code "119") (name "POT_5") (class "Default")
      (node (ref "U11") (pin "1") (pinfunction "X4_1") (pintype "bidirectional"))
      (node (ref "VR_4") (pin "2") (pinfunction "2_2") (pintype "passive"))
    )
    (net (code "120") (name "POT_6") (class "Default")
      (node (ref "U11") (pin "5") (pinfunction "X5_5") (pintype "bidirectional"))
      (node (ref "VR_6") (pin "2") (pinfunction "2_2") (pintype "passive"))
    )
    (net (code "121") (name "POT_7") (class "Default")
      (node (ref "U11") (pin "2") (pinfunction "X6_2") (pintype "bidirectional"))
      (node (ref "VR_7") (pin "2") (pinfunction "2_2") (pintype "passive"))
    )
    (net (code "122") (name "POT_8") (class "Default")
      (node (ref "U11") (pin "4") (pinfunction "X7_4") (pintype "bidirectional"))
      (node (ref "VR_8") (pin "2") (pinfunction "S_2") (pintype "passive"))
    )
    (net (code "123") (name "POT_MUX_ADC") (class "Default")
      (node (ref "U1") (pin "23") (pinfunction "GPIO16(ADC1)_23") (pintype "bidirectional"))
      (node (ref "U1") (pin "B23") (pinfunction "GPIO16(ADC1)_B23") (pintype "bidirectional"))
      (node (ref "U11") (pin "3") (pinfunction "X_3") (pintype "bidirectional"))
    )
    (net (code "124") (name "SD_CK") (class "Default")
      (node (ref "U1") (pin "7") (pinfunction "GPIO6(SDMMC1_CK)_7") (pintype "bidirectional"))
      (node (ref "U1") (pin "B7") (pinfunction "GPIO6(SDMMC1_CK)_B7") (pintype "bidirectional"))
      (node (ref "U2") (pin "P$5") (pinfunction "SCK_P$5") (pintype "bidirectional"))
    )
    (net (code "125") (name "SD_CMD") (class "Default")
      (node (ref "R1") (pin "1") (pinfunction "1_1") (pintype "passive"))
      (node (ref "U1") (pin "6") (pinfunction "GPIO5(SDMMC1_CMD)_6") (pintype "bidirectional"))
      (node (ref "U1") (pin "B6") (pinfunction "GPIO5(SDMMC1_CMD)_B6") (pintype "bidirectional"))
      (node (ref "U2") (pin "P$3") (pinfunction "CMD/DI_P$3") (pintype "bidirectional"))
    )
    (net (code "126") (name "SD_D0") (class "Default")
      (node (ref "R2") (pin "1") (pinfunction "1_1") (pintype "passive"))
      (node (ref "U1") (pin "5") (pinfunction "GPIO4(SDMMC1_D0)_5") (pintype "bidirectional"))
      (node (ref "U1") (pin "B5") (pinfunction "GPIO4(SDMMC1_D0)_B5") (pintype "bidirectional"))
      (node (ref "U2") (pin "P$7") (pinfunction "D0/DO_P$7") (pintype "bidirectional"))
    )
    (net (code "127") (name "SD_D1") (class "Default")
      (node (ref "R16") (pin "1") (pinfunction "1_1") (pintype "passive"))
      (node (ref "U1") (pin "4") (pinfunction "GPIO3(SDMMC1_D1)_4") (pintype "bidirectional"))
      (node (ref "U1") (pin "B4") (pinfunction "GPIO3(SDMMC1_D1)_B4") (pintype "bidirectional"))
      (node (ref "U2") (pin "P$8") (pinfunction "D1/RSV_P$8") (pintype "bidirectional"))
    )
    (net (code "128") (name "SD_D2") (class "Default")
      (node (ref "R3") (pin "1") (pinfunction "1_1") (pintype "passive"))
      (node (ref "U1") (pin "3") (pinfunction "GPIO2(SDMMC1_D2)_3") (pintype "bidirectional"))
      (node (ref "U1") (pin "B3") (pinfunction "GPIO2(SDMMC1_D2)_B3") (pintype "bidirectional"))
      (node (ref "U2") (pin "P$1") (pinfunction "D2/NC_P$1") (pintype "bidirectional"))
    )
    (net (code "129") (name "SD_D3") (class "Default")
      (node (ref "R4") (pin "1") (pinfunction "1_1") (pintype "passive"))
      (node (ref "U1") (pin "2") (pinfunction "GPIO1(SDMMC1_D3)_2") (pintype "bidirectional"))
      (node (ref "U1") (pin "B2") (pinfunction "GPIO1(SDMMC1_D3)_B2") (pintype "bidirectional"))
      (node (ref "U2") (pin "P$2") (pinfunction "D3/CS_P$2") (pintype "bidirectional"))
    )
    (net (code "130") (name "SPI1_CS") (class "Default")
      (node (ref "U1") (pin "8") (pinfunction "GPIO7(SPI1_NSS)_8") (pintype "bidirectional"))
      (node (ref "U1") (pin "B8") (pinfunction "GPIO7(SPI1_NSS)_B8") (pintype "bidirectional"))
      (node (ref "U8") (pin "7") (pinfunction "CS_7") (pintype "bidirectional"))
    )
    (net (code "131") (name "SPI1_MOSI") (class "Default")
      (node (ref "U1") (pin "11") (pinfunction "GPIO10(SPI1_MOSI)_11") (pintype "bidirectional"))
      (node (ref "U1") (pin "B11") (pinfunction "GPIO10(SPI1_MOSI)_B11") (pintype "bidirectional"))
      (node (ref "U8") (pin "4") (pinfunction "SDA_4") (pintype "bidirectional"))
    )
    (net (code "132") (name "SPI1_SCK") (class "Default")
      (node (ref "U1") (pin "9") (pinfunction "GPIO8(SPI1_SCK)_9") (pintype "bidirectional"))
      (node (ref "U1") (pin "B9") (pinfunction "GPIO8(SPI1_SCK)_B9") (pintype "bidirectional"))
      (node (ref "U8") (pin "3") (pinfunction "SCL_3") (pintype "bidirectional"))
    )
    (net (code "133") (name "TAC_SWITCH_1") (class "Default")
      (node (ref "S1") (pin "1") (pinfunction "1_1") (pintype "passive"))
      (node (ref "S1") (pin "2") (pinfunction "2_2") (pintype "passive"))
      (node (ref "U1") (pin "37") (pinfunction "GPIO30(USB_HS_D+)_37") (pintype "bidirectional"))
      (node (ref "U1") (pin "B37") (pinfunction "GPIO30(USB_HS_D+)_B37") (pintype "bidirectional"))
    )
    (net (code "134") (name "TAC_SWITCH_2") (class "Default")
      (node (ref "S2") (pin "1") (pinfunction "1_1") (pintype "passive"))
      (node (ref "S2") (pin "2") (pinfunction "2_2") (pintype "passive"))
      (node (ref "U1") (pin "36") (pinfunction "GPIO29(USB_HS_D_-)_36") (pintype "bidirectional"))
      (node (ref "U1") (pin "B36") (pinfunction "GPIO29(USB_HS_D_-)_B36") (pintype "bidirectional"))
    )
    (net (code "135") (name "USART1_RX") (class "Default")
      (node (ref "R64") (pin "2") (pinfunction "2_2") (pintype "passive"))
      (node (ref "U1") (pin "15") (pinfunction "GPIO14(USART1_RX)_15") (pintype "bidirectional"))
      (node (ref "U1") (pin "B15") (pinfunction "GPIO14(USART1_RX)_B15") (pintype "bidirectional"))
      (node (ref "U15") (pin "4") (pinfunction "OUT_4") (pintype "bidirectional"))
    )
    (net (code "136") (name "USART1_TX") (class "Default")
      (node (ref "R55") (pin "2") (pinfunction "2_2") (pintype "passive"))
      (node (ref "U1") (pin "14") (pinfunction "GPIO13(USART1_TX)_14") (pintype "bidirectional"))
      (node (ref "U1") (pin "B14") (pinfunction "GPIO13(USART1_TX)_B14") (pintype "bidirectional"))
    )
    (net (code "137") (name "V_AUDIOBIAS") (class "Default")
      (node (ref "R48") (pin "2") (pinfunction "2_2") (pintype "passive"))
      (node (ref "R62") (pin "2") (pinfunction "2_2") (pintype "passive"))
      (node (ref "U3") (pin "1") (pinfunction "OUT_1") (pintype "output"))
      (node (ref "U3") (pin "2") (pinfunction "-IN_2") (pintype "input"))
    )
    (net (code "138") (name "unconnected-(H1-MOUNT-PadB3,2)") (class "Default")
      (node (ref "H1") (pin "B3,2") (pinfunction "MOUNT_B3,2") (pintype "passive"))
    )
    (net (code "139") (name "unconnected-(H2-MOUNT-PadB3,2)") (class "Default")
      (node (ref "H2") (pin "B3,2") (pinfunction "MOUNT_B3,2") (pintype "passive"))
    )
    (net (code "140") (name "unconnected-(J7-SW-Pad2)") (class "Default")
      (node (ref "J7") (pin "2") (pinfunction "SW_2") (pintype "passive"))
    )
    (net (code "141") (name "unconnected-(J8-RING-Pad3)") (class "Default")
      (node (ref "J8") (pin "3") (pinfunction "RING_3") (pintype "passive"))
    )
    (net (code "142") (name "unconnected-(J8-RING_SW-Pad6)") (class "Default")
      (node (ref "J8") (pin "6") (pinfunction "RING_SW_6") (pintype "passive"))
    )
    (net (code "143") (name "unconnected-(J8-TIP_SW-Pad5)") (class "Default")
      (node (ref "J8") (pin "5") (pinfunction "TIP_SW_5") (pintype "passive"))
    )
    (net (code "144") (name "unconnected-(J9-RING-Pad3)") (class "Default")
      (node (ref "J9") (pin "3") (pinfunction "RING_3") (pintype "passive"))
    )
    (net (code "145") (name "unconnected-(J9-RING_SW-Pad6)") (class "Default")
      (node (ref "J9") (pin "6") (pinfunction "RING_SW_6") (pintype "passive"))
    )
    (net (code "146") (name "unconnected-(J10-RING_SW-Pad6)") (class "Default")
      (node (ref "J10") (pin "6") (pinfunction "RING_SW_6") (pintype "passive"))
    )
    (net (code "147") (name "unconnected-(J10-TIP_SW-Pad5)") (class "Default")
      (node (ref "J10") (pin "5") (pinfunction "TIP_SW_5") (pintype "passive"))
    )
    (net (code "148") (name "unconnected-(J12-RING-Pad3)") (class "Default")
      (node (ref "J12") (pin "3") (pinfunction "RING_3") (pintype "passive"))
    )
    (net (code "149") (name "unconnected-(J12-RING_SW-Pad6)") (class "Default")
      (node (ref "J12") (pin "6") (pinfunction "RING_SW_6") (pintype "passive"))
    )
    (net (code "150") (name "unconnected-(J12-TIP_SW-Pad5)") (class "Default")
      (node (ref "J12") (pin "5") (pinfunction "TIP_SW_5") (pintype "passive"))
    )
    (net (code "151") (name "unconnected-(J13-RING-Pad3)") (class "Default")
      (node (ref "J13") (pin "3") (pinfunction "RING_3") (pintype "passive"))
    )
    (net (code "152") (name "unconnected-(J13-RING_SW-Pad6)") (class "Default")
      (node (ref "J13") (pin "6") (pinfunction "RING_SW_6") (pintype "passive"))
    )
    (net (code "153") (name "unconnected-(J13-TIP_SW-Pad5)") (class "Default")
      (node (ref "J13") (pin "5") (pinfunction "TIP_SW_5") (pintype "passive"))
    )
    (net (code "154") (name "unconnected-(J_CV_OUT_1-NORM-Pad2)") (class "Default")
      (node (ref "J_CV_OUT_1") (pin "2") (pinfunction "NORM_2") (pintype "passive"))
    )
    (net (code "155") (name "unconnected-(J_CV_OUT_2-NORM-Pad2)") (class "Default")
      (node (ref "J_CV_OUT_2") (pin "2") (pinfunction "NORM_2") (pintype "passive"))
    )
    (net (code "156") (name "unconnected-(J_GATE_IN_1-NORM-Pad2)") (class "Default")
      (node (ref "J_GATE_IN_1") (pin "2") (pinfunction "NORM_2") (pintype "passive"))
    )
    (net (code "157") (name "unconnected-(J_GATE_OUT-NORM-Pad2)") (class "Default")
      (node (ref "J_GATE_OUT") (pin "2") (pinfunction "NORM_2") (pintype "passive"))
    )
    (net (code "158") (name "unconnected-(U5-LED8-Pad15)") (class "Default")
      (node (ref "U5") (pin "15") (pinfunction "LED8_15") (pintype "bidirectional"))
    )
    (net (code "159") (name "unconnected-(U5-LED9-Pad16)") (class "Default")
      (node (ref "U5") (pin "16") (pinfunction "LED9_16") (pintype "bidirectional"))
    )
    (net (code "160") (name "unconnected-(U5-LED10-Pad17)") (class "Default")
      (node (ref "U5") (pin "17") (pinfunction "LED10_17") (pintype "bidirectional"))
    )
    (net (code "161") (name "unconnected-(U5-LED11-Pad18)") (class "Default")
      (node (ref "U5") (pin "18") (pinfunction "LED11_18") (pintype "bidirectional"))
    )
    (net (code "162") (name "unconnected-(U5-LED12-Pad19)") (class "Default")
      (node (ref "U5") (pin "19") (pinfunction "LED12_19") (pintype "bidirectional"))
    )
    (net (code "163") (name "unconnected-(U5-LED13-Pad20)") (class "Default")
      (node (ref "U5") (pin "20") (pinfunction "LED13_20") (pintype "bidirectional"))
    )
    (net (code "164") (name "unconnected-(U5-LED14-Pad21)") (class "Default")
      (node (ref "U5") (pin "21") (pinfunction "LED14_21") (pintype "bidirectional"))
    )
    (net (code "165") (name "unconnected-(U5-LED15-Pad22)") (class "Default")
      (node (ref "U5") (pin "22") (pinfunction "LED15_22") (pintype "bidirectional"))
    )
    (net (code "166") (name "unconnected-(U7-PG-Pad8)") (class "Default")
      (node (ref "U7") (pin "8") (pinfunction "PG_8") (pintype "bidirectional"))
    )
    (net (code "167") (name "unconnected-(U16-CD4021_D2-Pad10A)") (class "Default")
      (node (ref "U16") (pin "10A") (pinfunction "CD4021_D2_10A") (pintype "bidirectional"))
    )
    (net (code "168") (name "unconnected-(U16-LED_B3_G-Pad8A)") (class "Default")
      (node (ref "U16") (pin "8A") (pinfunction "LED_B3_G_8A") (pintype "bidirectional"))
    )
    (net (code "169") (name "unconnected-(U16-LED_B3_R-Pad9A)") (class "Default")
      (node (ref "U16") (pin "9A") (pinfunction "LED_B3_R_9A") (pintype "bidirectional"))
    )
    (net (code "170") (name "unconnected-(U16-LED_B4_G-Pad2B)") (class "Default")
      (node (ref "U16") (pin "2B") (pinfunction "LED_B4_G_2B") (pintype "bidirectional"))
    )
    (net (code "171") (name "unconnected-(U16-LED_B4_R-Pad1B)") (class "Default")
      (node (ref "U16") (pin "1B") (pinfunction "LED_B4_R_1B") (pintype "bidirectional"))
    )
    (net (code "172") (name "unconnected-(U16-LED_B5_G-Pad4B)") (class "Default")
      (node (ref "U16") (pin "4B") (pinfunction "LED_B5_G_4B") (pintype "bidirectional"))
    )
    (net (code "173") (name "unconnected-(U16-LED_B5_R-Pad3B)") (class "Default")
      (node (ref "U16") (pin "3B") (pinfunction "LED_B5_R_3B") (pintype "bidirectional"))
    )
    (net (code "174") (name "unconnected-(U16-LED_B6_G-Pad6B)") (class "Default")
      (node (ref "U16") (pin "6B") (pinfunction "LED_B6_G_6B") (pintype "bidirectional"))
    )
    (net (code "175") (name "unconnected-(U16-LED_B6_R-Pad5B)") (class "Default")
      (node (ref "U16") (pin "5B") (pinfunction "LED_B6_R_5B") (pintype "bidirectional"))
    )
    (net (code "176") (name "unconnected-(U16-LED_B7_G-Pad7B)") (class "Default")
      (node (ref "U16") (pin "7B") (pinfunction "LED_B7_G_7B") (pintype "bidirectional"))
    )
    (net (code "177") (name "unconnected-(U16-LED_B7_R-Pad8B)") (class "Default")
      (node (ref "U16") (pin "8B") (pinfunction "LED_B7_R_8B") (pintype "bidirectional"))
    )
    (net (code "178") (name "unconnected-(U16-LED_B8_G-Pad9B)") (class "Default")
      (node (ref "U16") (pin "9B") (pinfunction "LED_B8_G_9B") (pintype "bidirectional"))
    )
    (net (code "179") (name "unconnected-(U16-LED_B8_R-Pad10B)") (class "Default")
      (node (ref "U16") (pin "10B") (pinfunction "LED_B8_R_10B") (pintype "bidirectional"))
    )
  )
)
